# Schematic.net
KiCad netlist of a schematic drawn in EAGLE
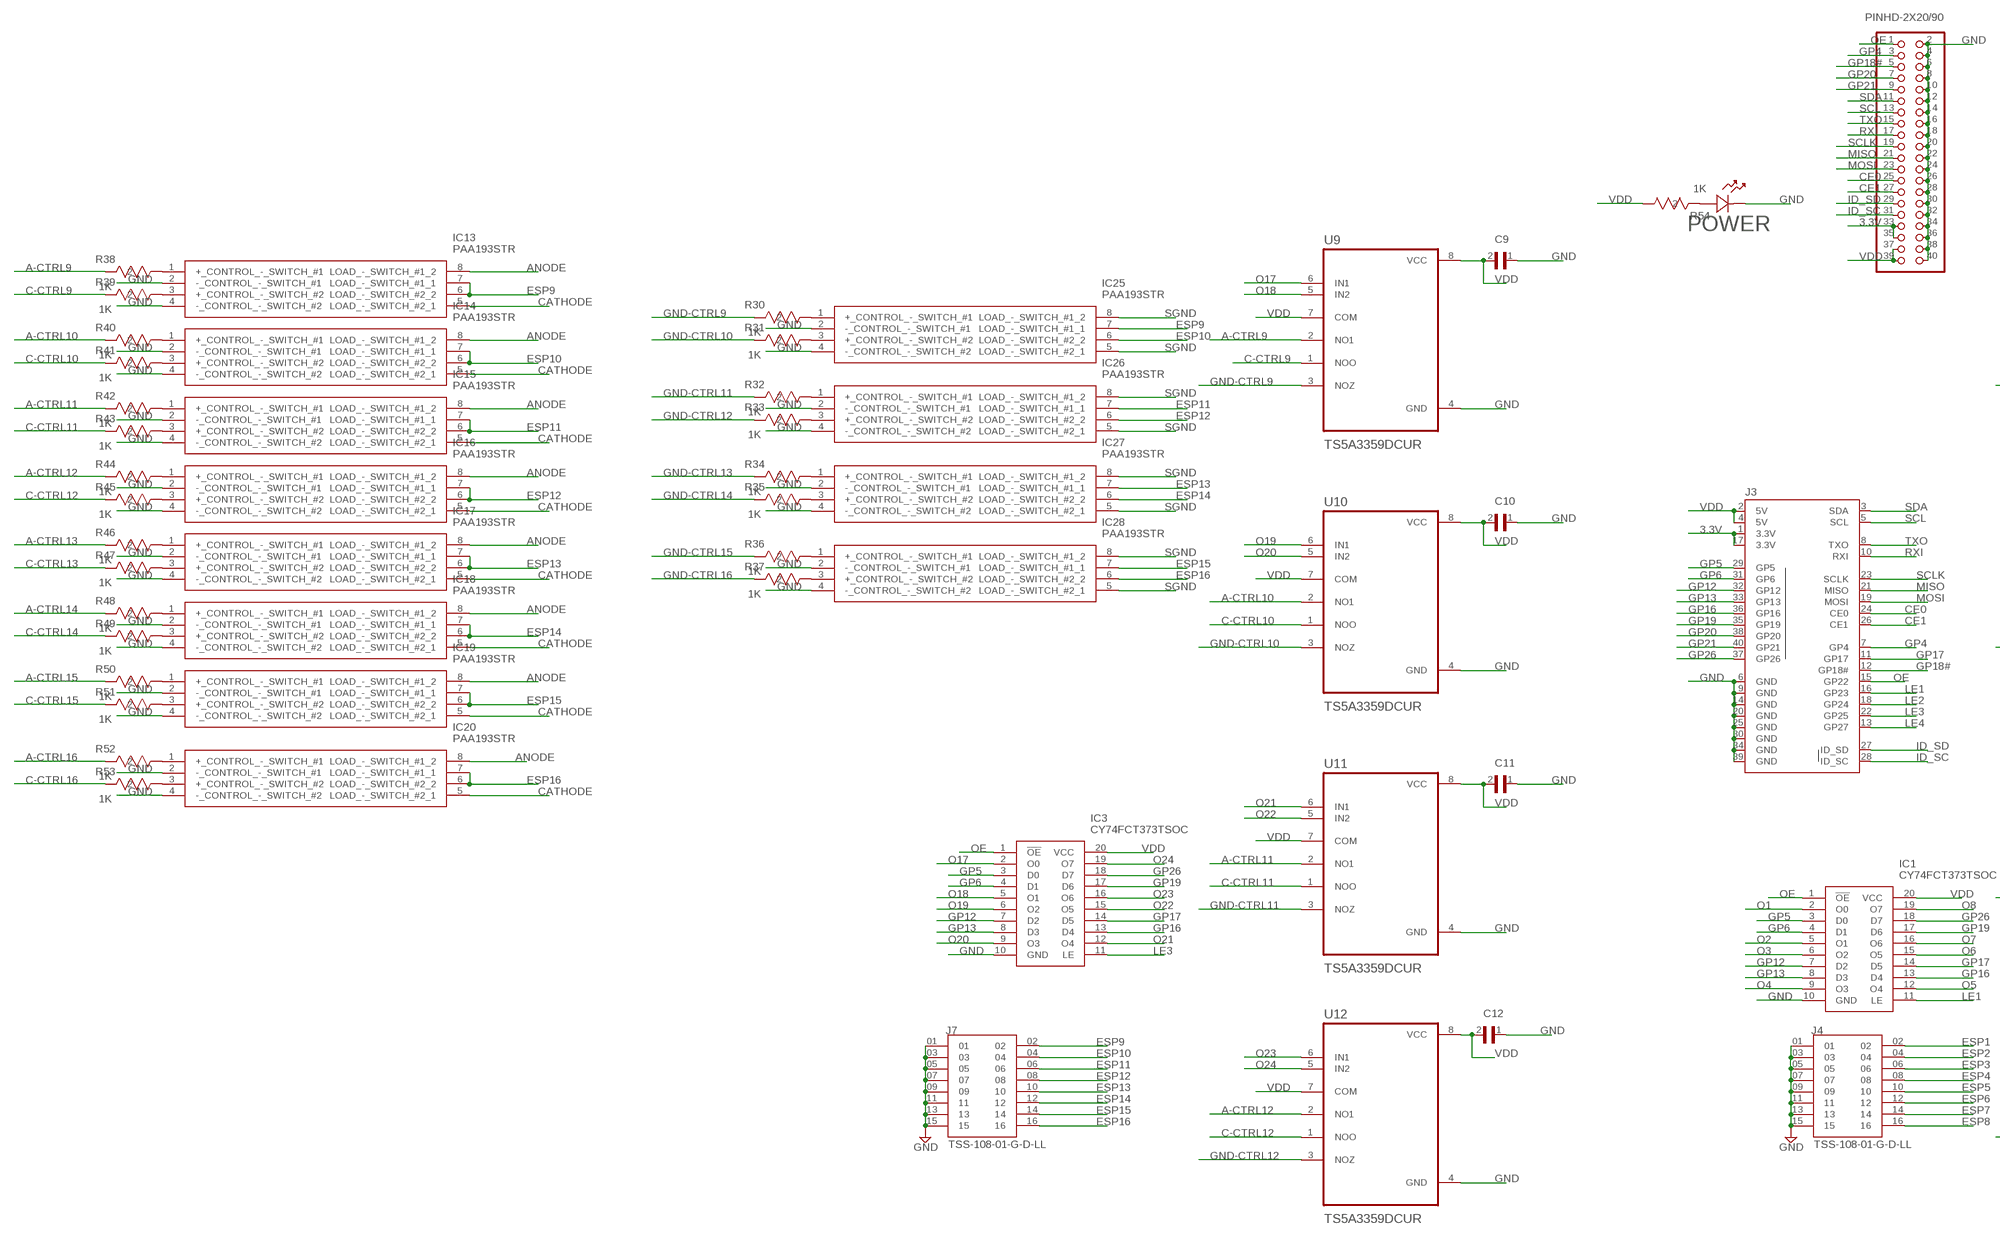
[diagram p0: schematic, sheet 1, part 1 of 3]
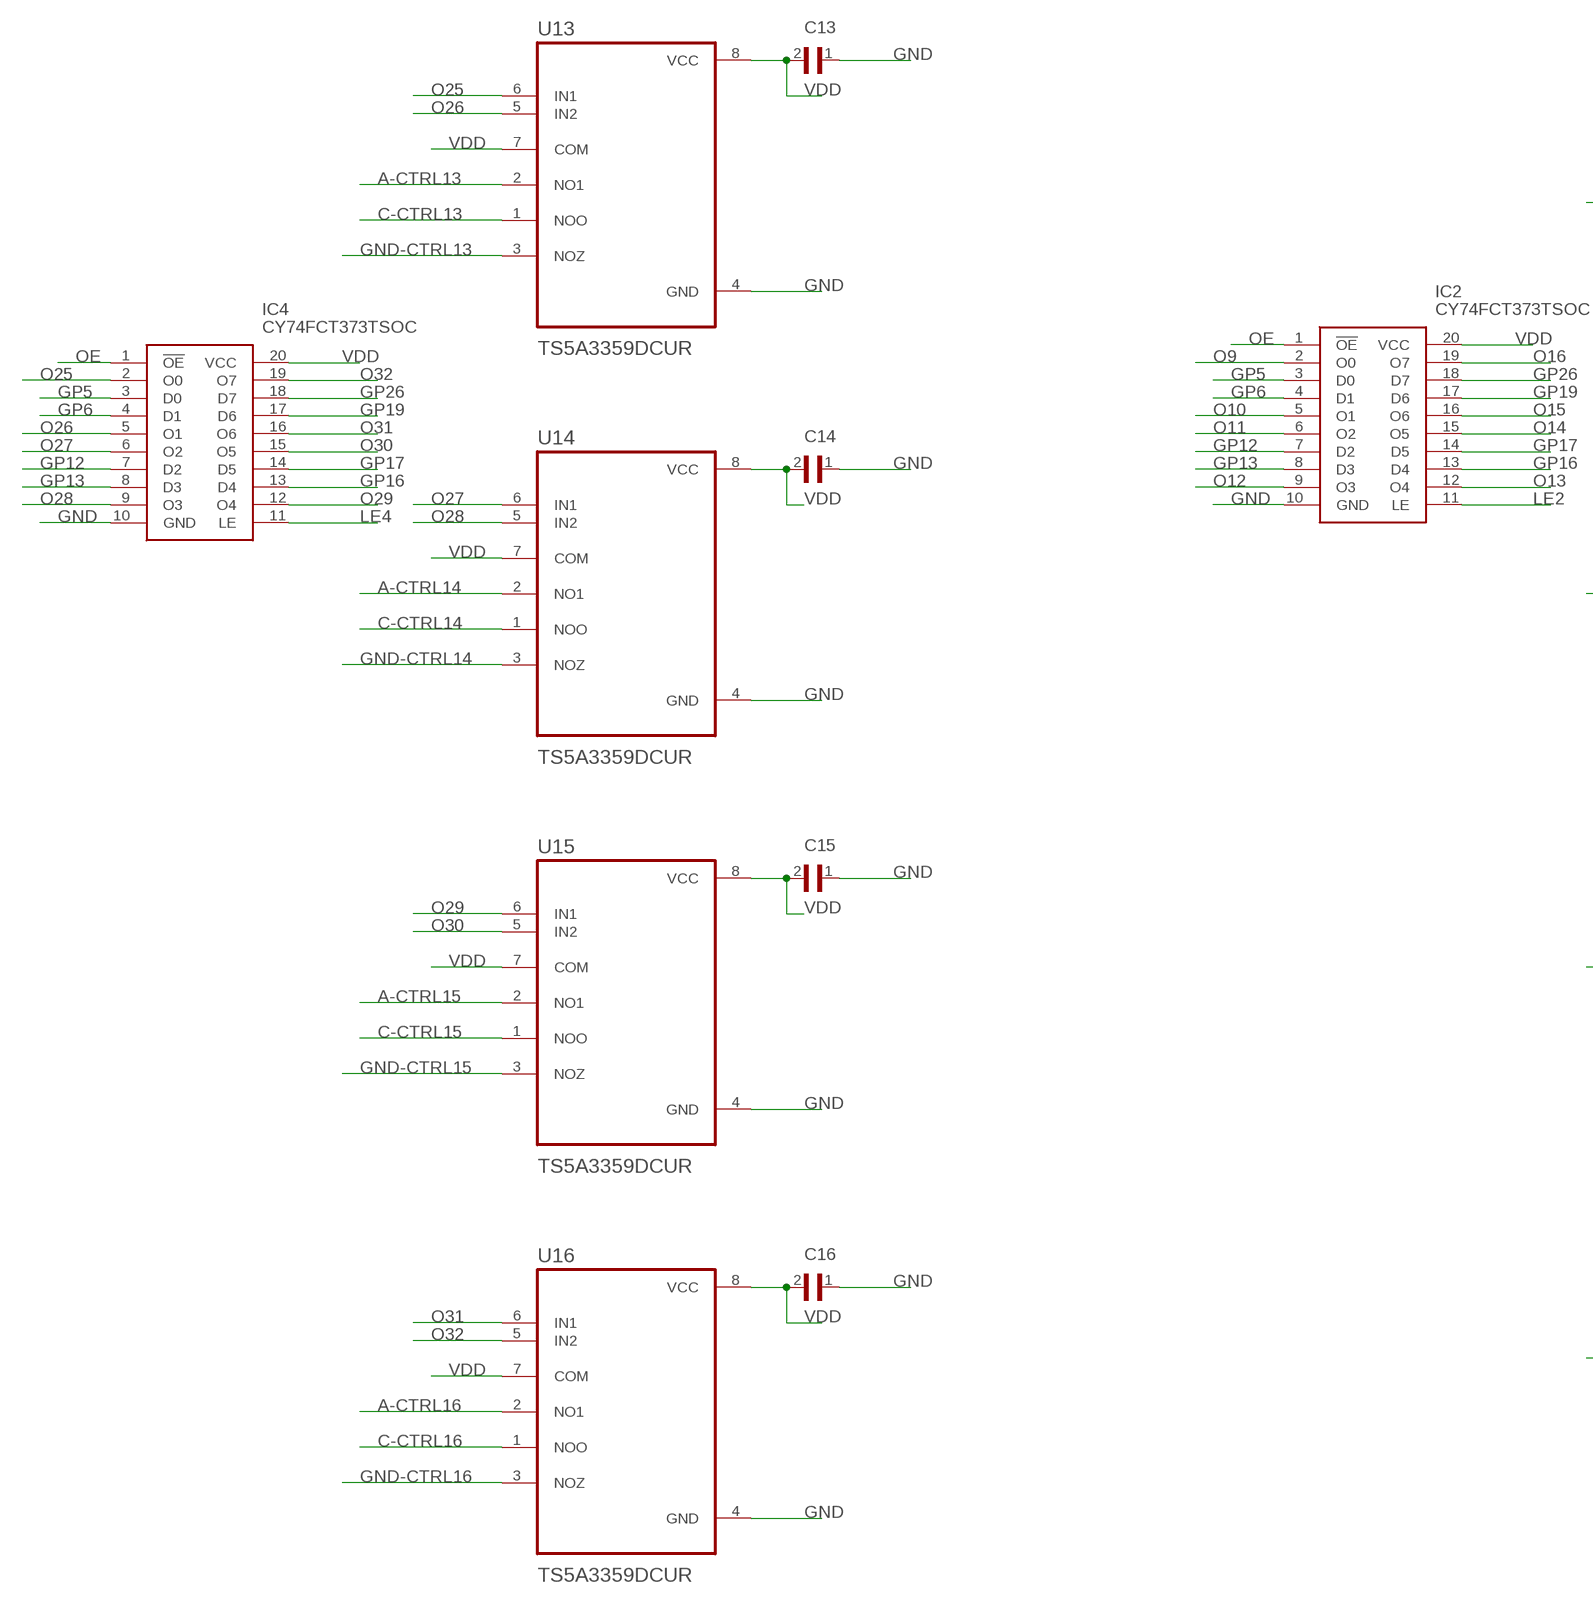
[diagram p1: schematic, sheet 1, part 2 of 3]
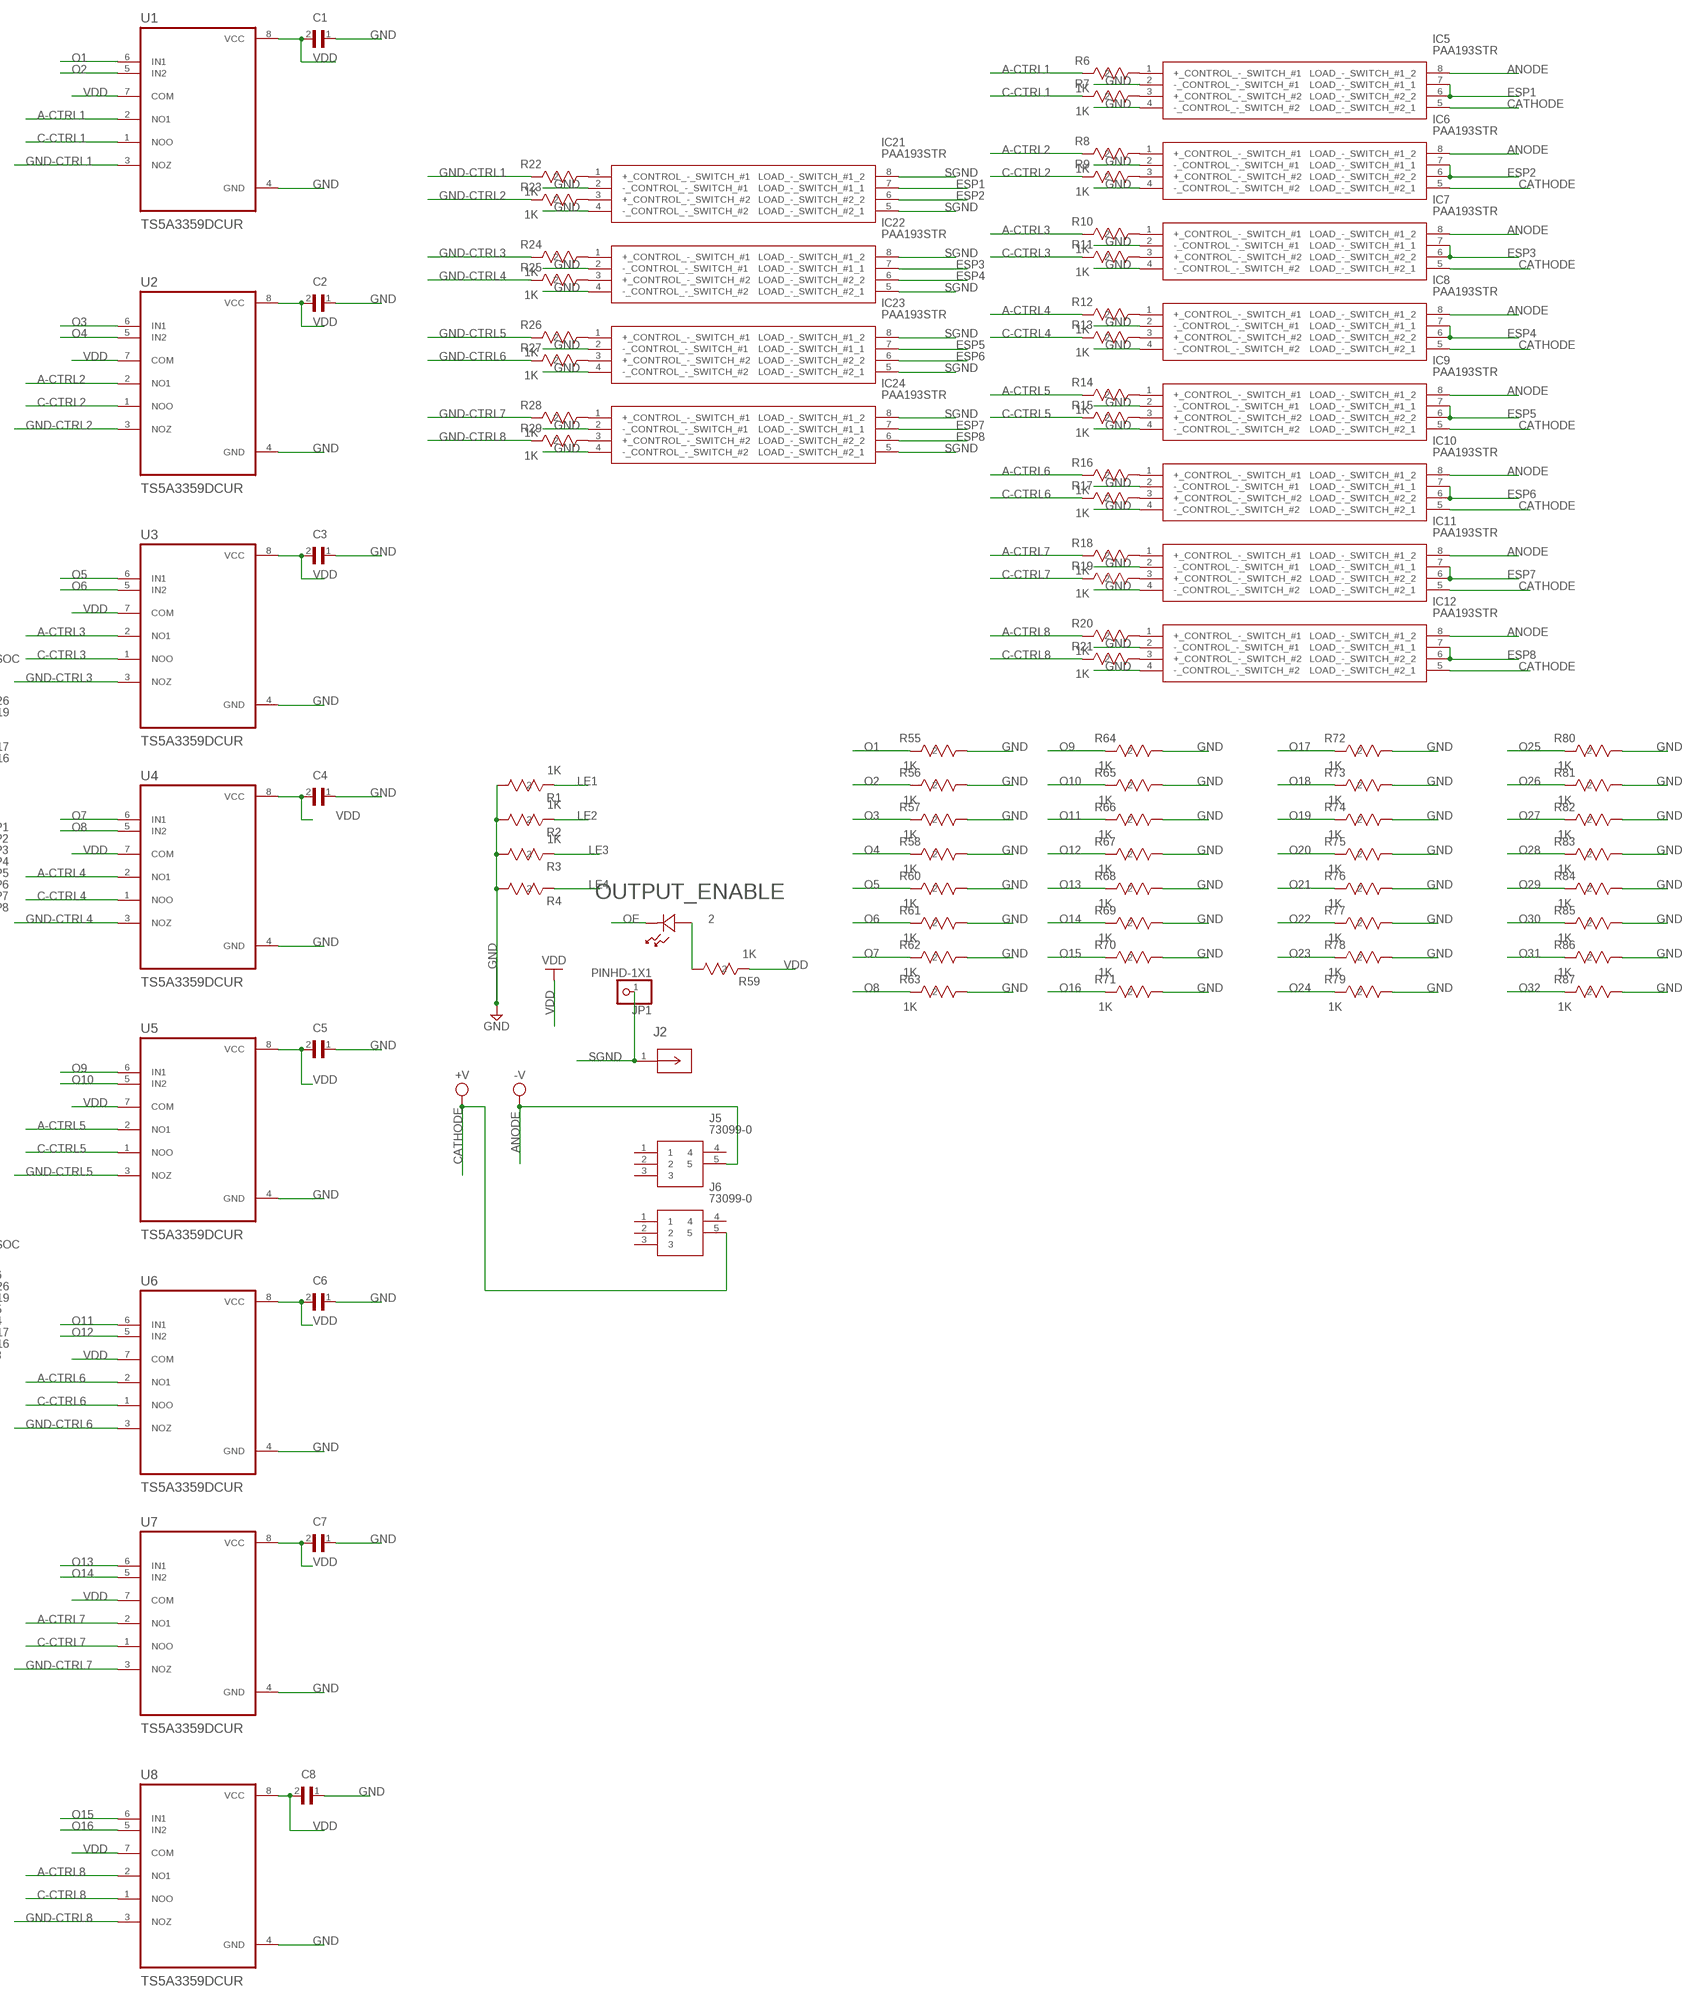
[diagram p2: schematic, sheet 1, part 3 of 3]

(export (version "E")
  (design (tool "Eeschema 10.0.6"))
  (components
    (comp (ref "C1")
      (value "CL05A104KA5NNNC")
      (footprint "eagle-import:CAPC1005X55N")
      (fields (field (name "MF") "Samsung Electro-Mechanics"))
      (libsource (lib "eagle-import") (part "CL05A104KA5NNNC"))
    )
    (comp (ref "C2")
      (value "CL05A104KA5NNNC")
      (footprint "eagle-import:CAPC1005X55N")
      (fields (field (name "MF") "Samsung Electro-Mechanics"))
      (libsource (lib "eagle-import") (part "CL05A104KA5NNNC"))
    )
    (comp (ref "C3")
      (value "CL05A104KA5NNNC")
      (footprint "eagle-import:CAPC1005X55N")
      (fields (field (name "MF") "Samsung Electro-Mechanics"))
      (libsource (lib "eagle-import") (part "CL05A104KA5NNNC"))
    )
    (comp (ref "C4")
      (value "CL05A104KA5NNNC")
      (footprint "eagle-import:CAPC1005X55N")
      (fields (field (name "MF") "Samsung Electro-Mechanics"))
      (libsource (lib "eagle-import") (part "CL05A104KA5NNNC"))
    )
    (comp (ref "C5")
      (value "CL05A104KA5NNNC")
      (footprint "eagle-import:CAPC1005X55N")
      (fields (field (name "MF") "Samsung Electro-Mechanics"))
      (libsource (lib "eagle-import") (part "CL05A104KA5NNNC"))
    )
    (comp (ref "C6")
      (value "CL05A104KA5NNNC")
      (footprint "eagle-import:CAPC1005X55N")
      (fields (field (name "MF") "Samsung Electro-Mechanics"))
      (libsource (lib "eagle-import") (part "CL05A104KA5NNNC"))
    )
    (comp (ref "C7")
      (value "CL05A104KA5NNNC")
      (footprint "eagle-import:CAPC1005X55N")
      (fields (field (name "MF") "Samsung Electro-Mechanics"))
      (libsource (lib "eagle-import") (part "CL05A104KA5NNNC"))
    )
    (comp (ref "C8")
      (value "CL05A104KA5NNNC")
      (footprint "eagle-import:CAPC1005X55N")
      (fields (field (name "MF") "Samsung Electro-Mechanics"))
      (libsource (lib "eagle-import") (part "CL05A104KA5NNNC"))
    )
    (comp (ref "C9")
      (value "CL05A104KA5NNNC")
      (footprint "eagle-import:CAPC1005X55N")
      (fields (field (name "MF") "Samsung Electro-Mechanics"))
      (libsource (lib "eagle-import") (part "CL05A104KA5NNNC"))
    )
    (comp (ref "C10")
      (value "CL05A104KA5NNNC")
      (footprint "eagle-import:CAPC1005X55N")
      (fields (field (name "MF") "Samsung Electro-Mechanics"))
      (libsource (lib "eagle-import") (part "CL05A104KA5NNNC"))
    )
    (comp (ref "C11")
      (value "CL05A104KA5NNNC")
      (footprint "eagle-import:CAPC1005X55N")
      (fields (field (name "MF") "Samsung Electro-Mechanics"))
      (libsource (lib "eagle-import") (part "CL05A104KA5NNNC"))
    )
    (comp (ref "C12")
      (value "CL05A104KA5NNNC")
      (footprint "eagle-import:CAPC1005X55N")
      (fields (field (name "MF") "Samsung Electro-Mechanics"))
      (libsource (lib "eagle-import") (part "CL05A104KA5NNNC"))
    )
    (comp (ref "C13")
      (value "CL05A104KA5NNNC")
      (footprint "eagle-import:CAPC1005X55N")
      (fields (field (name "MF") "Samsung Electro-Mechanics"))
      (libsource (lib "eagle-import") (part "CL05A104KA5NNNC"))
    )
    (comp (ref "C14")
      (value "CL05A104KA5NNNC")
      (footprint "eagle-import:CAPC1005X55N")
      (fields (field (name "MF") "Samsung Electro-Mechanics"))
      (libsource (lib "eagle-import") (part "CL05A104KA5NNNC"))
    )
    (comp (ref "C15")
      (value "CL05A104KA5NNNC")
      (footprint "eagle-import:CAPC1005X55N")
      (fields (field (name "MF") "Samsung Electro-Mechanics"))
      (libsource (lib "eagle-import") (part "CL05A104KA5NNNC"))
    )
    (comp (ref "C16")
      (value "CL05A104KA5NNNC")
      (footprint "eagle-import:CAPC1005X55N")
      (fields (field (name "MF") "Samsung Electro-Mechanics"))
      (libsource (lib "eagle-import") (part "CL05A104KA5NNNC"))
    )
    (comp (ref "IC1")
      (value "CY74FCT373TSOC")
      (footprint "eagle-import:SOIC127P1030X265-20N")
      (libsource (lib "eagle-import") (part "CY74FCT373TSOC"))
    )
    (comp (ref "IC2")
      (value "CY74FCT373TSOC")
      (footprint "eagle-import:SOIC127P1030X265-20N")
      (libsource (lib "eagle-import") (part "CY74FCT373TSOC"))
    )
    (comp (ref "IC3")
      (value "CY74FCT373TSOC")
      (footprint "eagle-import:SOIC127P1030X265-20N")
      (libsource (lib "eagle-import") (part "CY74FCT373TSOC"))
    )
    (comp (ref "IC4")
      (value "CY74FCT373TSOC")
      (footprint "eagle-import:SOIC127P1030X265-20N")
      (libsource (lib "eagle-import") (part "CY74FCT373TSOC"))
    )
    (comp (ref "IC5")
      (value "PAA193STR")
      (footprint "eagle-import:SOP254P952X457-8N")
      (fields (field (name "MOUSER_PART_NUMBER") "849-PAA193STR"))
      (libsource (lib "eagle-import") (part "PAA193STR"))
    )
    (comp (ref "IC6")
      (value "PAA193STR")
      (footprint "eagle-import:SOP254P952X457-8N")
      (fields (field (name "MOUSER_PART_NUMBER") "849-PAA193STR"))
      (libsource (lib "eagle-import") (part "PAA193STR"))
    )
    (comp (ref "IC7")
      (value "PAA193STR")
      (footprint "eagle-import:SOP254P952X457-8N")
      (fields (field (name "MOUSER_PART_NUMBER") "849-PAA193STR"))
      (libsource (lib "eagle-import") (part "PAA193STR"))
    )
    (comp (ref "IC8")
      (value "PAA193STR")
      (footprint "eagle-import:SOP254P952X457-8N")
      (fields (field (name "MOUSER_PART_NUMBER") "849-PAA193STR"))
      (libsource (lib "eagle-import") (part "PAA193STR"))
    )
    (comp (ref "IC9")
      (value "PAA193STR")
      (footprint "eagle-import:SOP254P952X457-8N")
      (fields (field (name "MOUSER_PART_NUMBER") "849-PAA193STR"))
      (libsource (lib "eagle-import") (part "PAA193STR"))
    )
    (comp (ref "IC10")
      (value "PAA193STR")
      (footprint "eagle-import:SOP254P952X457-8N")
      (fields (field (name "MOUSER_PART_NUMBER") "849-PAA193STR"))
      (libsource (lib "eagle-import") (part "PAA193STR"))
    )
    (comp (ref "IC11")
      (value "PAA193STR")
      (footprint "eagle-import:SOP254P952X457-8N")
      (fields (field (name "MOUSER_PART_NUMBER") "849-PAA193STR"))
      (libsource (lib "eagle-import") (part "PAA193STR"))
    )
    (comp (ref "IC12")
      (value "PAA193STR")
      (footprint "eagle-import:SOP254P952X457-8N")
      (fields (field (name "MOUSER_PART_NUMBER") "849-PAA193STR"))
      (libsource (lib "eagle-import") (part "PAA193STR"))
    )
    (comp (ref "IC13")
      (value "PAA193STR")
      (footprint "eagle-import:SOP254P952X457-8N")
      (fields (field (name "MOUSER_PART_NUMBER") "849-PAA193STR"))
      (libsource (lib "eagle-import") (part "PAA193STR"))
    )
    (comp (ref "IC14")
      (value "PAA193STR")
      (footprint "eagle-import:SOP254P952X457-8N")
      (fields (field (name "MOUSER_PART_NUMBER") "849-PAA193STR"))
      (libsource (lib "eagle-import") (part "PAA193STR"))
    )
    (comp (ref "IC15")
      (value "PAA193STR")
      (footprint "eagle-import:SOP254P952X457-8N")
      (fields (field (name "MOUSER_PART_NUMBER") "849-PAA193STR"))
      (libsource (lib "eagle-import") (part "PAA193STR"))
    )
    (comp (ref "IC16")
      (value "PAA193STR")
      (footprint "eagle-import:SOP254P952X457-8N")
      (fields (field (name "MOUSER_PART_NUMBER") "849-PAA193STR"))
      (libsource (lib "eagle-import") (part "PAA193STR"))
    )
    (comp (ref "IC17")
      (value "PAA193STR")
      (footprint "eagle-import:SOP254P952X457-8N")
      (fields (field (name "MOUSER_PART_NUMBER") "849-PAA193STR"))
      (libsource (lib "eagle-import") (part "PAA193STR"))
    )
    (comp (ref "IC18")
      (value "PAA193STR")
      (footprint "eagle-import:SOP254P952X457-8N")
      (fields (field (name "MOUSER_PART_NUMBER") "849-PAA193STR"))
      (libsource (lib "eagle-import") (part "PAA193STR"))
    )
    (comp (ref "IC19")
      (value "PAA193STR")
      (footprint "eagle-import:SOP254P952X457-8N")
      (fields (field (name "MOUSER_PART_NUMBER") "849-PAA193STR"))
      (libsource (lib "eagle-import") (part "PAA193STR"))
    )
    (comp (ref "IC20")
      (value "PAA193STR")
      (footprint "eagle-import:SOP254P952X457-8N")
      (fields (field (name "MOUSER_PART_NUMBER") "849-PAA193STR"))
      (libsource (lib "eagle-import") (part "PAA193STR"))
    )
    (comp (ref "IC21")
      (value "PAA193STR")
      (footprint "eagle-import:SOP254P952X457-8N")
      (fields (field (name "MOUSER_PART_NUMBER") "849-PAA193STR"))
      (libsource (lib "eagle-import") (part "PAA193STR"))
    )
    (comp (ref "IC22")
      (value "PAA193STR")
      (footprint "eagle-import:SOP254P952X457-8N")
      (fields (field (name "MOUSER_PART_NUMBER") "849-PAA193STR"))
      (libsource (lib "eagle-import") (part "PAA193STR"))
    )
    (comp (ref "IC23")
      (value "PAA193STR")
      (footprint "eagle-import:SOP254P952X457-8N")
      (fields (field (name "MOUSER_PART_NUMBER") "849-PAA193STR"))
      (libsource (lib "eagle-import") (part "PAA193STR"))
    )
    (comp (ref "IC24")
      (value "PAA193STR")
      (footprint "eagle-import:SOP254P952X457-8N")
      (fields (field (name "MOUSER_PART_NUMBER") "849-PAA193STR"))
      (libsource (lib "eagle-import") (part "PAA193STR"))
    )
    (comp (ref "IC25")
      (value "PAA193STR")
      (footprint "eagle-import:SOP254P952X457-8N")
      (fields (field (name "MOUSER_PART_NUMBER") "849-PAA193STR"))
      (libsource (lib "eagle-import") (part "PAA193STR"))
    )
    (comp (ref "IC26")
      (value "PAA193STR")
      (footprint "eagle-import:SOP254P952X457-8N")
      (fields (field (name "MOUSER_PART_NUMBER") "849-PAA193STR"))
      (libsource (lib "eagle-import") (part "PAA193STR"))
    )
    (comp (ref "IC27")
      (value "PAA193STR")
      (footprint "eagle-import:SOP254P952X457-8N")
      (fields (field (name "MOUSER_PART_NUMBER") "849-PAA193STR"))
      (libsource (lib "eagle-import") (part "PAA193STR"))
    )
    (comp (ref "IC28")
      (value "PAA193STR")
      (footprint "eagle-import:SOP254P952X457-8N")
      (fields (field (name "MOUSER_PART_NUMBER") "849-PAA193STR"))
      (libsource (lib "eagle-import") (part "PAA193STR"))
    )
    (comp (ref "J2")
      (value "FCR7350GCONN_FCR7350G_CLF")
      (footprint "eagle-import:CONN_FCR7350G_CLF")
      (fields
        (field (name "MANUFACTURER_PART_NUMBER") "FCR7350G")
        (field (name "COPYRIGHT") "Copyright (C) 2024 Ultra Librarian. All rights reserved.")
      )
      (libsource (lib "eagle-import") (part "FCR7350GCONN_FCR7350G_CLF"))
    )
    (comp (ref "J3")
      (value "RASPBERRYPI-40-PIN-GPIO_PTH_NO_SHROUD")
      (footprint "eagle-import:2X20")
      (fields (field (name "SPICEPREFIX") "X"))
      (libsource (lib "eagle-import") (part "RASPBERRYPI-40-PIN-GPIO_PTH_NO_SHROUD"))
    )
    (comp (ref "J4")
      (value "TSS-108-01-G-D-LL")
      (footprint "eagle-import:SAMTEC_TSS-108-01-G-D-LL")
      (libsource (lib "eagle-import") (part "TSS-108-01-G-D-LL"))
    )
    (comp (ref "J5")
      (value "73099-0")
      (footprint "eagle-import:730990")
      (fields (field (name "MOUSER_PART_NUMBER") "565-73099-0"))
      (libsource (lib "eagle-import") (part "73099-0"))
    )
    (comp (ref "J6")
      (value "73099-0")
      (footprint "eagle-import:730990")
      (fields (field (name "MOUSER_PART_NUMBER") "565-73099-0"))
      (libsource (lib "eagle-import") (part "73099-0"))
    )
    (comp (ref "J7")
      (value "TSS-108-01-G-D-LL")
      (footprint "eagle-import:SAMTEC_TSS-108-01-G-D-LL")
      (libsource (lib "eagle-import") (part "TSS-108-01-G-D-LL"))
    )
    (comp (ref "JP1")
      (value "PINHD-1X1")
      (footprint "eagle-import:1X01")
      (fields (field (name "MANUFACTURER") "Generic"))
      (libsource (lib "eagle-import") (part "PINHD-1X1"))
    )
    (comp (ref "JP4")
      (value "PINHD-2X20/90")
      (footprint "eagle-import:2X20_90")
      (fields (field (name "MANUFACTURER") "Generic"))
      (libsource (lib "eagle-import") (part "PINHD-2X20/90"))
    )
    (comp (ref "OUTPUT_ENABLE")
      (value "LTST-C190GKTLED_LTST-C190CKT_LTO")
      (footprint "eagle-import:LED_LTST-C190CKT_LTO")
      (fields
        (field (name "MANUFACTURER_PART_NUMBER") "LTST-C190GKT")
        (field (name "COPYRIGHT") "Copyright (C) 2024 Ultra Librarian. All rights reserved.")
      )
      (libsource (lib "eagle-import") (part "LTST-C190GKTLED_LTST-C190CKT_LTO"))
    )
    (comp (ref "POWER")
      (value "LTST-C190GKTLED_LTST-C190CKT_LTO")
      (footprint "eagle-import:LED_LTST-C190CKT_LTO")
      (fields
        (field (name "MANUFACTURER_PART_NUMBER") "LTST-C190GKT")
        (field (name "COPYRIGHT") "Copyright (C) 2024 Ultra Librarian. All rights reserved.")
      )
      (libsource (lib "eagle-import") (part "LTST-C190GKTLED_LTST-C190CKT_LTO"))
    )
    (comp (ref "R1")
      (value "1K")
      (footprint "eagle-import:RC0402N_YAG")
      (fields
        (field (name "MANUFACTURER_PART_NUMBER") "RC0402JR-071KL")
        (field (name "COPYRIGHT") "Copyright (C) 2023 Ultra Librarian. All rights reserved.")
      )
      (libsource (lib "eagle-import") (part "RC0402JR-071KLRC0402N_YAG"))
    )
    (comp (ref "R2")
      (value "1K")
      (footprint "eagle-import:RC0402N_YAG")
      (fields
        (field (name "MANUFACTURER_PART_NUMBER") "RC0402JR-071KL")
        (field (name "COPYRIGHT") "Copyright (C) 2023 Ultra Librarian. All rights reserved.")
      )
      (libsource (lib "eagle-import") (part "RC0402JR-071KLRC0402N_YAG"))
    )
    (comp (ref "R3")
      (value "1K")
      (footprint "eagle-import:RC0402N_YAG")
      (fields
        (field (name "MANUFACTURER_PART_NUMBER") "RC0402JR-071KL")
        (field (name "COPYRIGHT") "Copyright (C) 2023 Ultra Librarian. All rights reserved.")
      )
      (libsource (lib "eagle-import") (part "RC0402JR-071KLRC0402N_YAG"))
    )
    (comp (ref "R4")
      (value "RC0402JR-071KLRC0402N_YAG")
      (footprint "eagle-import:RC0402N_YAG")
      (fields
        (field (name "MANUFACTURER_PART_NUMBER") "RC0402JR-071KL")
        (field (name "COPYRIGHT") "Copyright (C) 2023 Ultra Librarian. All rights reserved.")
      )
      (libsource (lib "eagle-import") (part "RC0402JR-071KLRC0402N_YAG"))
    )
    (comp (ref "R6")
      (value "1K")
      (footprint "eagle-import:RC0402N_YAG")
      (fields
        (field (name "MANUFACTURER_PART_NUMBER") "RC0402JR-071KL")
        (field (name "COPYRIGHT") "Copyright (C) 2023 Ultra Librarian. All rights reserved.")
      )
      (libsource (lib "eagle-import") (part "RC0402JR-071KLRC0402N_YAG"))
    )
    (comp (ref "R7")
      (value "1K")
      (footprint "eagle-import:RC0402N_YAG")
      (fields
        (field (name "MANUFACTURER_PART_NUMBER") "RC0402JR-071KL")
        (field (name "COPYRIGHT") "Copyright (C) 2023 Ultra Librarian. All rights reserved.")
      )
      (libsource (lib "eagle-import") (part "RC0402JR-071KLRC0402N_YAG"))
    )
    (comp (ref "R8")
      (value "1K")
      (footprint "eagle-import:RC0402N_YAG")
      (fields
        (field (name "MANUFACTURER_PART_NUMBER") "RC0402JR-071KL")
        (field (name "COPYRIGHT") "Copyright (C) 2023 Ultra Librarian. All rights reserved.")
      )
      (libsource (lib "eagle-import") (part "RC0402JR-071KLRC0402N_YAG"))
    )
    (comp (ref "R9")
      (value "1K")
      (footprint "eagle-import:RC0402N_YAG")
      (fields
        (field (name "MANUFACTURER_PART_NUMBER") "RC0402JR-071KL")
        (field (name "COPYRIGHT") "Copyright (C) 2023 Ultra Librarian. All rights reserved.")
      )
      (libsource (lib "eagle-import") (part "RC0402JR-071KLRC0402N_YAG"))
    )
    (comp (ref "R10")
      (value "1K")
      (footprint "eagle-import:RC0402N_YAG")
      (fields
        (field (name "MANUFACTURER_PART_NUMBER") "RC0402JR-071KL")
        (field (name "COPYRIGHT") "Copyright (C) 2023 Ultra Librarian. All rights reserved.")
      )
      (libsource (lib "eagle-import") (part "RC0402JR-071KLRC0402N_YAG"))
    )
    (comp (ref "R11")
      (value "1K")
      (footprint "eagle-import:RC0402N_YAG")
      (fields
        (field (name "MANUFACTURER_PART_NUMBER") "RC0402JR-071KL")
        (field (name "COPYRIGHT") "Copyright (C) 2023 Ultra Librarian. All rights reserved.")
      )
      (libsource (lib "eagle-import") (part "RC0402JR-071KLRC0402N_YAG"))
    )
    (comp (ref "R12")
      (value "1K")
      (footprint "eagle-import:RC0402N_YAG")
      (fields
        (field (name "MANUFACTURER_PART_NUMBER") "RC0402JR-071KL")
        (field (name "COPYRIGHT") "Copyright (C) 2023 Ultra Librarian. All rights reserved.")
      )
      (libsource (lib "eagle-import") (part "RC0402JR-071KLRC0402N_YAG"))
    )
    (comp (ref "R13")
      (value "1K")
      (footprint "eagle-import:RC0402N_YAG")
      (fields
        (field (name "MANUFACTURER_PART_NUMBER") "RC0402JR-071KL")
        (field (name "COPYRIGHT") "Copyright (C) 2023 Ultra Librarian. All rights reserved.")
      )
      (libsource (lib "eagle-import") (part "RC0402JR-071KLRC0402N_YAG"))
    )
    (comp (ref "R14")
      (value "1K")
      (footprint "eagle-import:RC0402N_YAG")
      (fields
        (field (name "MANUFACTURER_PART_NUMBER") "RC0402JR-071KL")
        (field (name "COPYRIGHT") "Copyright (C) 2023 Ultra Librarian. All rights reserved.")
      )
      (libsource (lib "eagle-import") (part "RC0402JR-071KLRC0402N_YAG"))
    )
    (comp (ref "R15")
      (value "1K")
      (footprint "eagle-import:RC0402N_YAG")
      (fields
        (field (name "MANUFACTURER_PART_NUMBER") "RC0402JR-071KL")
        (field (name "COPYRIGHT") "Copyright (C) 2023 Ultra Librarian. All rights reserved.")
      )
      (libsource (lib "eagle-import") (part "RC0402JR-071KLRC0402N_YAG"))
    )
    (comp (ref "R16")
      (value "1K")
      (footprint "eagle-import:RC0402N_YAG")
      (fields
        (field (name "MANUFACTURER_PART_NUMBER") "RC0402JR-071KL")
        (field (name "COPYRIGHT") "Copyright (C) 2023 Ultra Librarian. All rights reserved.")
      )
      (libsource (lib "eagle-import") (part "RC0402JR-071KLRC0402N_YAG"))
    )
    (comp (ref "R17")
      (value "1K")
      (footprint "eagle-import:RC0402N_YAG")
      (fields
        (field (name "MANUFACTURER_PART_NUMBER") "RC0402JR-071KL")
        (field (name "COPYRIGHT") "Copyright (C) 2023 Ultra Librarian. All rights reserved.")
      )
      (libsource (lib "eagle-import") (part "RC0402JR-071KLRC0402N_YAG"))
    )
    (comp (ref "R18")
      (value "1K")
      (footprint "eagle-import:RC0402N_YAG")
      (fields
        (field (name "MANUFACTURER_PART_NUMBER") "RC0402JR-071KL")
        (field (name "COPYRIGHT") "Copyright (C) 2023 Ultra Librarian. All rights reserved.")
      )
      (libsource (lib "eagle-import") (part "RC0402JR-071KLRC0402N_YAG"))
    )
    (comp (ref "R19")
      (value "1K")
      (footprint "eagle-import:RC0402N_YAG")
      (fields
        (field (name "MANUFACTURER_PART_NUMBER") "RC0402JR-071KL")
        (field (name "COPYRIGHT") "Copyright (C) 2023 Ultra Librarian. All rights reserved.")
      )
      (libsource (lib "eagle-import") (part "RC0402JR-071KLRC0402N_YAG"))
    )
    (comp (ref "R20")
      (value "1K")
      (footprint "eagle-import:RC0402N_YAG")
      (fields
        (field (name "MANUFACTURER_PART_NUMBER") "RC0402JR-071KL")
        (field (name "COPYRIGHT") "Copyright (C) 2023 Ultra Librarian. All rights reserved.")
      )
      (libsource (lib "eagle-import") (part "RC0402JR-071KLRC0402N_YAG"))
    )
    (comp (ref "R21")
      (value "1K")
      (footprint "eagle-import:RC0402N_YAG")
      (fields
        (field (name "MANUFACTURER_PART_NUMBER") "RC0402JR-071KL")
        (field (name "COPYRIGHT") "Copyright (C) 2023 Ultra Librarian. All rights reserved.")
      )
      (libsource (lib "eagle-import") (part "RC0402JR-071KLRC0402N_YAG"))
    )
    (comp (ref "R22")
      (value "1K")
      (footprint "eagle-import:RC0402N_YAG")
      (fields
        (field (name "MANUFACTURER_PART_NUMBER") "RC0402JR-071KL")
        (field (name "COPYRIGHT") "Copyright (C) 2023 Ultra Librarian. All rights reserved.")
      )
      (libsource (lib "eagle-import") (part "RC0402JR-071KLRC0402N_YAG"))
    )
    (comp (ref "R23")
      (value "1K")
      (footprint "eagle-import:RC0402N_YAG")
      (fields
        (field (name "MANUFACTURER_PART_NUMBER") "RC0402JR-071KL")
        (field (name "COPYRIGHT") "Copyright (C) 2023 Ultra Librarian. All rights reserved.")
      )
      (libsource (lib "eagle-import") (part "RC0402JR-071KLRC0402N_YAG"))
    )
    (comp (ref "R24")
      (value "1K")
      (footprint "eagle-import:RC0402N_YAG")
      (fields
        (field (name "MANUFACTURER_PART_NUMBER") "RC0402JR-071KL")
        (field (name "COPYRIGHT") "Copyright (C) 2023 Ultra Librarian. All rights reserved.")
      )
      (libsource (lib "eagle-import") (part "RC0402JR-071KLRC0402N_YAG"))
    )
    (comp (ref "R25")
      (value "1K")
      (footprint "eagle-import:RC0402N_YAG")
      (fields
        (field (name "MANUFACTURER_PART_NUMBER") "RC0402JR-071KL")
        (field (name "COPYRIGHT") "Copyright (C) 2023 Ultra Librarian. All rights reserved.")
      )
      (libsource (lib "eagle-import") (part "RC0402JR-071KLRC0402N_YAG"))
    )
    (comp (ref "R26")
      (value "1K")
      (footprint "eagle-import:RC0402N_YAG")
      (fields
        (field (name "MANUFACTURER_PART_NUMBER") "RC0402JR-071KL")
        (field (name "COPYRIGHT") "Copyright (C) 2023 Ultra Librarian. All rights reserved.")
      )
      (libsource (lib "eagle-import") (part "RC0402JR-071KLRC0402N_YAG"))
    )
    (comp (ref "R27")
      (value "1K")
      (footprint "eagle-import:RC0402N_YAG")
      (fields
        (field (name "MANUFACTURER_PART_NUMBER") "RC0402JR-071KL")
        (field (name "COPYRIGHT") "Copyright (C) 2023 Ultra Librarian. All rights reserved.")
      )
      (libsource (lib "eagle-import") (part "RC0402JR-071KLRC0402N_YAG"))
    )
    (comp (ref "R28")
      (value "1K")
      (footprint "eagle-import:RC0402N_YAG")
      (fields
        (field (name "MANUFACTURER_PART_NUMBER") "RC0402JR-071KL")
        (field (name "COPYRIGHT") "Copyright (C) 2023 Ultra Librarian. All rights reserved.")
      )
      (libsource (lib "eagle-import") (part "RC0402JR-071KLRC0402N_YAG"))
    )
    (comp (ref "R29")
      (value "1K")
      (footprint "eagle-import:RC0402N_YAG")
      (fields
        (field (name "MANUFACTURER_PART_NUMBER") "RC0402JR-071KL")
        (field (name "COPYRIGHT") "Copyright (C) 2023 Ultra Librarian. All rights reserved.")
      )
      (libsource (lib "eagle-import") (part "RC0402JR-071KLRC0402N_YAG"))
    )
    (comp (ref "R30")
      (value "1K")
      (footprint "eagle-import:RC0402N_YAG")
      (fields
        (field (name "MANUFACTURER_PART_NUMBER") "RC0402JR-071KL")
        (field (name "COPYRIGHT") "Copyright (C) 2023 Ultra Librarian. All rights reserved.")
      )
      (libsource (lib "eagle-import") (part "RC0402JR-071KLRC0402N_YAG"))
    )
    (comp (ref "R31")
      (value "1K")
      (footprint "eagle-import:RC0402N_YAG")
      (fields
        (field (name "MANUFACTURER_PART_NUMBER") "RC0402JR-071KL")
        (field (name "COPYRIGHT") "Copyright (C) 2023 Ultra Librarian. All rights reserved.")
      )
      (libsource (lib "eagle-import") (part "RC0402JR-071KLRC0402N_YAG"))
    )
    (comp (ref "R32")
      (value "1K")
      (footprint "eagle-import:RC0402N_YAG")
      (fields
        (field (name "MANUFACTURER_PART_NUMBER") "RC0402JR-071KL")
        (field (name "COPYRIGHT") "Copyright (C) 2023 Ultra Librarian. All rights reserved.")
      )
      (libsource (lib "eagle-import") (part "RC0402JR-071KLRC0402N_YAG"))
    )
    (comp (ref "R33")
      (value "1K")
      (footprint "eagle-import:RC0402N_YAG")
      (fields
        (field (name "MANUFACTURER_PART_NUMBER") "RC0402JR-071KL")
        (field (name "COPYRIGHT") "Copyright (C) 2023 Ultra Librarian. All rights reserved.")
      )
      (libsource (lib "eagle-import") (part "RC0402JR-071KLRC0402N_YAG"))
    )
    (comp (ref "R34")
      (value "1K")
      (footprint "eagle-import:RC0402N_YAG")
      (fields
        (field (name "MANUFACTURER_PART_NUMBER") "RC0402JR-071KL")
        (field (name "COPYRIGHT") "Copyright (C) 2023 Ultra Librarian. All rights reserved.")
      )
      (libsource (lib "eagle-import") (part "RC0402JR-071KLRC0402N_YAG"))
    )
    (comp (ref "R35")
      (value "1K")
      (footprint "eagle-import:RC0402N_YAG")
      (fields
        (field (name "MANUFACTURER_PART_NUMBER") "RC0402JR-071KL")
        (field (name "COPYRIGHT") "Copyright (C) 2023 Ultra Librarian. All rights reserved.")
      )
      (libsource (lib "eagle-import") (part "RC0402JR-071KLRC0402N_YAG"))
    )
    (comp (ref "R36")
      (value "1K")
      (footprint "eagle-import:RC0402N_YAG")
      (fields
        (field (name "MANUFACTURER_PART_NUMBER") "RC0402JR-071KL")
        (field (name "COPYRIGHT") "Copyright (C) 2023 Ultra Librarian. All rights reserved.")
      )
      (libsource (lib "eagle-import") (part "RC0402JR-071KLRC0402N_YAG"))
    )
    (comp (ref "R37")
      (value "1K")
      (footprint "eagle-import:RC0402N_YAG")
      (fields
        (field (name "MANUFACTURER_PART_NUMBER") "RC0402JR-071KL")
        (field (name "COPYRIGHT") "Copyright (C) 2023 Ultra Librarian. All rights reserved.")
      )
      (libsource (lib "eagle-import") (part "RC0402JR-071KLRC0402N_YAG"))
    )
    (comp (ref "R38")
      (value "1K")
      (footprint "eagle-import:RC0402N_YAG")
      (fields
        (field (name "MANUFACTURER_PART_NUMBER") "RC0402JR-071KL")
        (field (name "COPYRIGHT") "Copyright (C) 2023 Ultra Librarian. All rights reserved.")
      )
      (libsource (lib "eagle-import") (part "RC0402JR-071KLRC0402N_YAG"))
    )
    (comp (ref "R39")
      (value "1K")
      (footprint "eagle-import:RC0402N_YAG")
      (fields
        (field (name "MANUFACTURER_PART_NUMBER") "RC0402JR-071KL")
        (field (name "COPYRIGHT") "Copyright (C) 2023 Ultra Librarian. All rights reserved.")
      )
      (libsource (lib "eagle-import") (part "RC0402JR-071KLRC0402N_YAG"))
    )
    (comp (ref "R40")
      (value "1K")
      (footprint "eagle-import:RC0402N_YAG")
      (fields
        (field (name "MANUFACTURER_PART_NUMBER") "RC0402JR-071KL")
        (field (name "COPYRIGHT") "Copyright (C) 2023 Ultra Librarian. All rights reserved.")
      )
      (libsource (lib "eagle-import") (part "RC0402JR-071KLRC0402N_YAG"))
    )
    (comp (ref "R41")
      (value "1K")
      (footprint "eagle-import:RC0402N_YAG")
      (fields
        (field (name "MANUFACTURER_PART_NUMBER") "RC0402JR-071KL")
        (field (name "COPYRIGHT") "Copyright (C) 2023 Ultra Librarian. All rights reserved.")
      )
      (libsource (lib "eagle-import") (part "RC0402JR-071KLRC0402N_YAG"))
    )
    (comp (ref "R42")
      (value "1K")
      (footprint "eagle-import:RC0402N_YAG")
      (fields
        (field (name "MANUFACTURER_PART_NUMBER") "RC0402JR-071KL")
        (field (name "COPYRIGHT") "Copyright (C) 2023 Ultra Librarian. All rights reserved.")
      )
      (libsource (lib "eagle-import") (part "RC0402JR-071KLRC0402N_YAG"))
    )
    (comp (ref "R43")
      (value "1K")
      (footprint "eagle-import:RC0402N_YAG")
      (fields
        (field (name "MANUFACTURER_PART_NUMBER") "RC0402JR-071KL")
        (field (name "COPYRIGHT") "Copyright (C) 2023 Ultra Librarian. All rights reserved.")
      )
      (libsource (lib "eagle-import") (part "RC0402JR-071KLRC0402N_YAG"))
    )
    (comp (ref "R44")
      (value "1K")
      (footprint "eagle-import:RC0402N_YAG")
      (fields
        (field (name "MANUFACTURER_PART_NUMBER") "RC0402JR-071KL")
        (field (name "COPYRIGHT") "Copyright (C) 2023 Ultra Librarian. All rights reserved.")
      )
      (libsource (lib "eagle-import") (part "RC0402JR-071KLRC0402N_YAG"))
    )
    (comp (ref "R45")
      (value "1K")
      (footprint "eagle-import:RC0402N_YAG")
      (fields
        (field (name "MANUFACTURER_PART_NUMBER") "RC0402JR-071KL")
        (field (name "COPYRIGHT") "Copyright (C) 2023 Ultra Librarian. All rights reserved.")
      )
      (libsource (lib "eagle-import") (part "RC0402JR-071KLRC0402N_YAG"))
    )
    (comp (ref "R46")
      (value "1K")
      (footprint "eagle-import:RC0402N_YAG")
      (fields
        (field (name "MANUFACTURER_PART_NUMBER") "RC0402JR-071KL")
        (field (name "COPYRIGHT") "Copyright (C) 2023 Ultra Librarian. All rights reserved.")
      )
      (libsource (lib "eagle-import") (part "RC0402JR-071KLRC0402N_YAG"))
    )
    (comp (ref "R47")
      (value "1K")
      (footprint "eagle-import:RC0402N_YAG")
      (fields
        (field (name "MANUFACTURER_PART_NUMBER") "RC0402JR-071KL")
        (field (name "COPYRIGHT") "Copyright (C) 2023 Ultra Librarian. All rights reserved.")
      )
      (libsource (lib "eagle-import") (part "RC0402JR-071KLRC0402N_YAG"))
    )
    (comp (ref "R48")
      (value "1K")
      (footprint "eagle-import:RC0402N_YAG")
      (fields
        (field (name "MANUFACTURER_PART_NUMBER") "RC0402JR-071KL")
        (field (name "COPYRIGHT") "Copyright (C) 2023 Ultra Librarian. All rights reserved.")
      )
      (libsource (lib "eagle-import") (part "RC0402JR-071KLRC0402N_YAG"))
    )
    (comp (ref "R49")
      (value "1K")
      (footprint "eagle-import:RC0402N_YAG")
      (fields
        (field (name "MANUFACTURER_PART_NUMBER") "RC0402JR-071KL")
        (field (name "COPYRIGHT") "Copyright (C) 2023 Ultra Librarian. All rights reserved.")
      )
      (libsource (lib "eagle-import") (part "RC0402JR-071KLRC0402N_YAG"))
    )
    (comp (ref "R50")
      (value "1K")
      (footprint "eagle-import:RC0402N_YAG")
      (fields
        (field (name "MANUFACTURER_PART_NUMBER") "RC0402JR-071KL")
        (field (name "COPYRIGHT") "Copyright (C) 2023 Ultra Librarian. All rights reserved.")
      )
      (libsource (lib "eagle-import") (part "RC0402JR-071KLRC0402N_YAG"))
    )
    (comp (ref "R51")
      (value "1K")
      (footprint "eagle-import:RC0402N_YAG")
      (fields
        (field (name "MANUFACTURER_PART_NUMBER") "RC0402JR-071KL")
        (field (name "COPYRIGHT") "Copyright (C) 2023 Ultra Librarian. All rights reserved.")
      )
      (libsource (lib "eagle-import") (part "RC0402JR-071KLRC0402N_YAG"))
    )
    (comp (ref "R52")
      (value "1K")
      (footprint "eagle-import:RC0402N_YAG")
      (fields
        (field (name "MANUFACTURER_PART_NUMBER") "RC0402JR-071KL")
        (field (name "COPYRIGHT") "Copyright (C) 2023 Ultra Librarian. All rights reserved.")
      )
      (libsource (lib "eagle-import") (part "RC0402JR-071KLRC0402N_YAG"))
    )
    (comp (ref "R53")
      (value "1K")
      (footprint "eagle-import:RC0402N_YAG")
      (fields
        (field (name "MANUFACTURER_PART_NUMBER") "RC0402JR-071KL")
        (field (name "COPYRIGHT") "Copyright (C) 2023 Ultra Librarian. All rights reserved.")
      )
      (libsource (lib "eagle-import") (part "RC0402JR-071KLRC0402N_YAG"))
    )
    (comp (ref "R54")
      (value "1K")
      (footprint "eagle-import:RC0402N_YAG")
      (fields
        (field (name "MANUFACTURER_PART_NUMBER") "RC0402JR-071KL")
        (field (name "COPYRIGHT") "Copyright (C) 2023 Ultra Librarian. All rights reserved.")
      )
      (libsource (lib "eagle-import") (part "RC0402JR-071KLRC0402N_YAG"))
    )
    (comp (ref "R55")
      (value "1K")
      (footprint "eagle-import:RC0402N_YAG")
      (fields
        (field (name "MANUFACTURER_PART_NUMBER") "RC0402JR-071KL")
        (field (name "COPYRIGHT") "Copyright (C) 2023 Ultra Librarian. All rights reserved.")
      )
      (libsource (lib "eagle-import") (part "RC0402JR-071KLRC0402N_YAG"))
    )
    (comp (ref "R56")
      (value "1K")
      (footprint "eagle-import:RC0402N_YAG")
      (fields
        (field (name "MANUFACTURER_PART_NUMBER") "RC0402JR-071KL")
        (field (name "COPYRIGHT") "Copyright (C) 2023 Ultra Librarian. All rights reserved.")
      )
      (libsource (lib "eagle-import") (part "RC0402JR-071KLRC0402N_YAG"))
    )
    (comp (ref "R57")
      (value "1K")
      (footprint "eagle-import:RC0402N_YAG")
      (fields
        (field (name "MANUFACTURER_PART_NUMBER") "RC0402JR-071KL")
        (field (name "COPYRIGHT") "Copyright (C) 2023 Ultra Librarian. All rights reserved.")
      )
      (libsource (lib "eagle-import") (part "RC0402JR-071KLRC0402N_YAG"))
    )
    (comp (ref "R58")
      (value "1K")
      (footprint "eagle-import:RC0402N_YAG")
      (fields
        (field (name "MANUFACTURER_PART_NUMBER") "RC0402JR-071KL")
        (field (name "COPYRIGHT") "Copyright (C) 2023 Ultra Librarian. All rights reserved.")
      )
      (libsource (lib "eagle-import") (part "RC0402JR-071KLRC0402N_YAG"))
    )
    (comp (ref "R59")
      (value "1K")
      (footprint "eagle-import:RC0402N_YAG")
      (fields
        (field (name "MANUFACTURER_PART_NUMBER") "RC0402JR-071KL")
        (field (name "COPYRIGHT") "Copyright (C) 2023 Ultra Librarian. All rights reserved.")
      )
      (libsource (lib "eagle-import") (part "RC0402JR-071KLRC0402N_YAG"))
    )
    (comp (ref "R60")
      (value "1K")
      (footprint "eagle-import:RC0402N_YAG")
      (fields
        (field (name "MANUFACTURER_PART_NUMBER") "RC0402JR-071KL")
        (field (name "COPYRIGHT") "Copyright (C) 2023 Ultra Librarian. All rights reserved.")
      )
      (libsource (lib "eagle-import") (part "RC0402JR-071KLRC0402N_YAG"))
    )
    (comp (ref "R61")
      (value "1K")
      (footprint "eagle-import:RC0402N_YAG")
      (fields
        (field (name "MANUFACTURER_PART_NUMBER") "RC0402JR-071KL")
        (field (name "COPYRIGHT") "Copyright (C) 2023 Ultra Librarian. All rights reserved.")
      )
      (libsource (lib "eagle-import") (part "RC0402JR-071KLRC0402N_YAG"))
    )
    (comp (ref "R62")
      (value "1K")
      (footprint "eagle-import:RC0402N_YAG")
      (fields
        (field (name "MANUFACTURER_PART_NUMBER") "RC0402JR-071KL")
        (field (name "COPYRIGHT") "Copyright (C) 2023 Ultra Librarian. All rights reserved.")
      )
      (libsource (lib "eagle-import") (part "RC0402JR-071KLRC0402N_YAG"))
    )
    (comp (ref "R63")
      (value "1K")
      (footprint "eagle-import:RC0402N_YAG")
      (fields
        (field (name "MANUFACTURER_PART_NUMBER") "RC0402JR-071KL")
        (field (name "COPYRIGHT") "Copyright (C) 2023 Ultra Librarian. All rights reserved.")
      )
      (libsource (lib "eagle-import") (part "RC0402JR-071KLRC0402N_YAG"))
    )
    (comp (ref "R64")
      (value "1K")
      (footprint "eagle-import:RC0402N_YAG")
      (fields
        (field (name "MANUFACTURER_PART_NUMBER") "RC0402JR-071KL")
        (field (name "COPYRIGHT") "Copyright (C) 2023 Ultra Librarian. All rights reserved.")
      )
      (libsource (lib "eagle-import") (part "RC0402JR-071KLRC0402N_YAG"))
    )
    (comp (ref "R65")
      (value "1K")
      (footprint "eagle-import:RC0402N_YAG")
      (fields
        (field (name "MANUFACTURER_PART_NUMBER") "RC0402JR-071KL")
        (field (name "COPYRIGHT") "Copyright (C) 2023 Ultra Librarian. All rights reserved.")
      )
      (libsource (lib "eagle-import") (part "RC0402JR-071KLRC0402N_YAG"))
    )
    (comp (ref "R66")
      (value "1K")
      (footprint "eagle-import:RC0402N_YAG")
      (fields
        (field (name "MANUFACTURER_PART_NUMBER") "RC0402JR-071KL")
        (field (name "COPYRIGHT") "Copyright (C) 2023 Ultra Librarian. All rights reserved.")
      )
      (libsource (lib "eagle-import") (part "RC0402JR-071KLRC0402N_YAG"))
    )
    (comp (ref "R67")
      (value "1K")
      (footprint "eagle-import:RC0402N_YAG")
      (fields
        (field (name "MANUFACTURER_PART_NUMBER") "RC0402JR-071KL")
        (field (name "COPYRIGHT") "Copyright (C) 2023 Ultra Librarian. All rights reserved.")
      )
      (libsource (lib "eagle-import") (part "RC0402JR-071KLRC0402N_YAG"))
    )
    (comp (ref "R68")
      (value "1K")
      (footprint "eagle-import:RC0402N_YAG")
      (fields
        (field (name "MANUFACTURER_PART_NUMBER") "RC0402JR-071KL")
        (field (name "COPYRIGHT") "Copyright (C) 2023 Ultra Librarian. All rights reserved.")
      )
      (libsource (lib "eagle-import") (part "RC0402JR-071KLRC0402N_YAG"))
    )
    (comp (ref "R69")
      (value "1K")
      (footprint "eagle-import:RC0402N_YAG")
      (fields
        (field (name "MANUFACTURER_PART_NUMBER") "RC0402JR-071KL")
        (field (name "COPYRIGHT") "Copyright (C) 2023 Ultra Librarian. All rights reserved.")
      )
      (libsource (lib "eagle-import") (part "RC0402JR-071KLRC0402N_YAG"))
    )
    (comp (ref "R70")
      (value "1K")
      (footprint "eagle-import:RC0402N_YAG")
      (fields
        (field (name "MANUFACTURER_PART_NUMBER") "RC0402JR-071KL")
        (field (name "COPYRIGHT") "Copyright (C) 2023 Ultra Librarian. All rights reserved.")
      )
      (libsource (lib "eagle-import") (part "RC0402JR-071KLRC0402N_YAG"))
    )
    (comp (ref "R71")
      (value "1K")
      (footprint "eagle-import:RC0402N_YAG")
      (fields
        (field (name "MANUFACTURER_PART_NUMBER") "RC0402JR-071KL")
        (field (name "COPYRIGHT") "Copyright (C) 2023 Ultra Librarian. All rights reserved.")
      )
      (libsource (lib "eagle-import") (part "RC0402JR-071KLRC0402N_YAG"))
    )
    (comp (ref "R72")
      (value "1K")
      (footprint "eagle-import:RC0402N_YAG")
      (fields
        (field (name "MANUFACTURER_PART_NUMBER") "RC0402JR-071KL")
        (field (name "COPYRIGHT") "Copyright (C) 2023 Ultra Librarian. All rights reserved.")
      )
      (libsource (lib "eagle-import") (part "RC0402JR-071KLRC0402N_YAG"))
    )
    (comp (ref "R73")
      (value "1K")
      (footprint "eagle-import:RC0402N_YAG")
      (fields
        (field (name "MANUFACTURER_PART_NUMBER") "RC0402JR-071KL")
        (field (name "COPYRIGHT") "Copyright (C) 2023 Ultra Librarian. All rights reserved.")
      )
      (libsource (lib "eagle-import") (part "RC0402JR-071KLRC0402N_YAG"))
    )
    (comp (ref "R74")
      (value "1K")
      (footprint "eagle-import:RC0402N_YAG")
      (fields
        (field (name "MANUFACTURER_PART_NUMBER") "RC0402JR-071KL")
        (field (name "COPYRIGHT") "Copyright (C) 2023 Ultra Librarian. All rights reserved.")
      )
      (libsource (lib "eagle-import") (part "RC0402JR-071KLRC0402N_YAG"))
    )
    (comp (ref "R75")
      (value "1K")
      (footprint "eagle-import:RC0402N_YAG")
      (fields
        (field (name "MANUFACTURER_PART_NUMBER") "RC0402JR-071KL")
        (field (name "COPYRIGHT") "Copyright (C) 2023 Ultra Librarian. All rights reserved.")
      )
      (libsource (lib "eagle-import") (part "RC0402JR-071KLRC0402N_YAG"))
    )
    (comp (ref "R76")
      (value "1K")
      (footprint "eagle-import:RC0402N_YAG")
      (fields
        (field (name "MANUFACTURER_PART_NUMBER") "RC0402JR-071KL")
        (field (name "COPYRIGHT") "Copyright (C) 2023 Ultra Librarian. All rights reserved.")
      )
      (libsource (lib "eagle-import") (part "RC0402JR-071KLRC0402N_YAG"))
    )
    (comp (ref "R77")
      (value "1K")
      (footprint "eagle-import:RC0402N_YAG")
      (fields
        (field (name "MANUFACTURER_PART_NUMBER") "RC0402JR-071KL")
        (field (name "COPYRIGHT") "Copyright (C) 2023 Ultra Librarian. All rights reserved.")
      )
      (libsource (lib "eagle-import") (part "RC0402JR-071KLRC0402N_YAG"))
    )
    (comp (ref "R78")
      (value "1K")
      (footprint "eagle-import:RC0402N_YAG")
      (fields
        (field (name "MANUFACTURER_PART_NUMBER") "RC0402JR-071KL")
        (field (name "COPYRIGHT") "Copyright (C) 2023 Ultra Librarian. All rights reserved.")
      )
      (libsource (lib "eagle-import") (part "RC0402JR-071KLRC0402N_YAG"))
    )
    (comp (ref "R79")
      (value "1K")
      (footprint "eagle-import:RC0402N_YAG")
      (fields
        (field (name "MANUFACTURER_PART_NUMBER") "RC0402JR-071KL")
        (field (name "COPYRIGHT") "Copyright (C) 2023 Ultra Librarian. All rights reserved.")
      )
      (libsource (lib "eagle-import") (part "RC0402JR-071KLRC0402N_YAG"))
    )
    (comp (ref "R80")
      (value "1K")
      (footprint "eagle-import:RC0402N_YAG")
      (fields
        (field (name "MANUFACTURER_PART_NUMBER") "RC0402JR-071KL")
        (field (name "COPYRIGHT") "Copyright (C) 2023 Ultra Librarian. All rights reserved.")
      )
      (libsource (lib "eagle-import") (part "RC0402JR-071KLRC0402N_YAG"))
    )
    (comp (ref "R81")
      (value "1K")
      (footprint "eagle-import:RC0402N_YAG")
      (fields
        (field (name "MANUFACTURER_PART_NUMBER") "RC0402JR-071KL")
        (field (name "COPYRIGHT") "Copyright (C) 2023 Ultra Librarian. All rights reserved.")
      )
      (libsource (lib "eagle-import") (part "RC0402JR-071KLRC0402N_YAG"))
    )
    (comp (ref "R82")
      (value "1K")
      (footprint "eagle-import:RC0402N_YAG")
      (fields
        (field (name "MANUFACTURER_PART_NUMBER") "RC0402JR-071KL")
        (field (name "COPYRIGHT") "Copyright (C) 2023 Ultra Librarian. All rights reserved.")
      )
      (libsource (lib "eagle-import") (part "RC0402JR-071KLRC0402N_YAG"))
    )
    (comp (ref "R83")
      (value "1K")
      (footprint "eagle-import:RC0402N_YAG")
      (fields
        (field (name "MANUFACTURER_PART_NUMBER") "RC0402JR-071KL")
        (field (name "COPYRIGHT") "Copyright (C) 2023 Ultra Librarian. All rights reserved.")
      )
      (libsource (lib "eagle-import") (part "RC0402JR-071KLRC0402N_YAG"))
    )
    (comp (ref "R84")
      (value "1K")
      (footprint "eagle-import:RC0402N_YAG")
      (fields
        (field (name "MANUFACTURER_PART_NUMBER") "RC0402JR-071KL")
        (field (name "COPYRIGHT") "Copyright (C) 2023 Ultra Librarian. All rights reserved.")
      )
      (libsource (lib "eagle-import") (part "RC0402JR-071KLRC0402N_YAG"))
    )
    (comp (ref "R85")
      (value "1K")
      (footprint "eagle-import:RC0402N_YAG")
      (fields
        (field (name "MANUFACTURER_PART_NUMBER") "RC0402JR-071KL")
        (field (name "COPYRIGHT") "Copyright (C) 2023 Ultra Librarian. All rights reserved.")
      )
      (libsource (lib "eagle-import") (part "RC0402JR-071KLRC0402N_YAG"))
    )
    (comp (ref "R86")
      (value "1K")
      (footprint "eagle-import:RC0402N_YAG")
      (fields
        (field (name "MANUFACTURER_PART_NUMBER") "RC0402JR-071KL")
        (field (name "COPYRIGHT") "Copyright (C) 2023 Ultra Librarian. All rights reserved.")
      )
      (libsource (lib "eagle-import") (part "RC0402JR-071KLRC0402N_YAG"))
    )
    (comp (ref "R87")
      (value "1K")
      (footprint "eagle-import:RC0402N_YAG")
      (fields
        (field (name "MANUFACTURER_PART_NUMBER") "RC0402JR-071KL")
        (field (name "COPYRIGHT") "Copyright (C) 2023 Ultra Librarian. All rights reserved.")
      )
      (libsource (lib "eagle-import") (part "RC0402JR-071KLRC0402N_YAG"))
    )
    (comp (ref "U1")
      (value "TS5A3359DCUR")
      (footprint "eagle-import:SOP50P310X90-8N")
      (libsource (lib "eagle-import") (part "TS5A3359DCUR"))
    )
    (comp (ref "U2")
      (value "TS5A3359DCUR")
      (footprint "eagle-import:SOP50P310X90-8N")
      (libsource (lib "eagle-import") (part "TS5A3359DCUR"))
    )
    (comp (ref "U3")
      (value "TS5A3359DCUR")
      (footprint "eagle-import:SOP50P310X90-8N")
      (libsource (lib "eagle-import") (part "TS5A3359DCUR"))
    )
    (comp (ref "U4")
      (value "TS5A3359DCUR")
      (footprint "eagle-import:SOP50P310X90-8N")
      (libsource (lib "eagle-import") (part "TS5A3359DCUR"))
    )
    (comp (ref "U5")
      (value "TS5A3359DCUR")
      (footprint "eagle-import:SOP50P310X90-8N")
      (libsource (lib "eagle-import") (part "TS5A3359DCUR"))
    )
    (comp (ref "U6")
      (value "TS5A3359DCUR")
      (footprint "eagle-import:SOP50P310X90-8N")
      (libsource (lib "eagle-import") (part "TS5A3359DCUR"))
    )
    (comp (ref "U7")
      (value "TS5A3359DCUR")
      (footprint "eagle-import:SOP50P310X90-8N")
      (libsource (lib "eagle-import") (part "TS5A3359DCUR"))
    )
    (comp (ref "U8")
      (value "TS5A3359DCUR")
      (footprint "eagle-import:SOP50P310X90-8N")
      (libsource (lib "eagle-import") (part "TS5A3359DCUR"))
    )
    (comp (ref "U9")
      (value "TS5A3359DCUR")
      (footprint "eagle-import:SOP50P310X90-8N")
      (libsource (lib "eagle-import") (part "TS5A3359DCUR"))
    )
    (comp (ref "U10")
      (value "TS5A3359DCUR")
      (footprint "eagle-import:SOP50P310X90-8N")
      (libsource (lib "eagle-import") (part "TS5A3359DCUR"))
    )
    (comp (ref "U11")
      (value "TS5A3359DCUR")
      (footprint "eagle-import:SOP50P310X90-8N")
      (libsource (lib "eagle-import") (part "TS5A3359DCUR"))
    )
    (comp (ref "U12")
      (value "TS5A3359DCUR")
      (footprint "eagle-import:SOP50P310X90-8N")
      (libsource (lib "eagle-import") (part "TS5A3359DCUR"))
    )
    (comp (ref "U13")
      (value "TS5A3359DCUR")
      (footprint "eagle-import:SOP50P310X90-8N")
      (libsource (lib "eagle-import") (part "TS5A3359DCUR"))
    )
    (comp (ref "U14")
      (value "TS5A3359DCUR")
      (footprint "eagle-import:SOP50P310X90-8N")
      (libsource (lib "eagle-import") (part "TS5A3359DCUR"))
    )
    (comp (ref "U15")
      (value "TS5A3359DCUR")
      (footprint "eagle-import:SOP50P310X90-8N")
      (libsource (lib "eagle-import") (part "TS5A3359DCUR"))
    )
    (comp (ref "U16")
      (value "TS5A3359DCUR")
      (footprint "eagle-import:SOP50P310X90-8N")
      (libsource (lib "eagle-import") (part "TS5A3359DCUR"))
    )
  )
  (nets
    (net (code "1") (name "+V") (class "Default")
      (node (ref "IC10") (pin "5") (pinfunction "LOAD_-_SWITCH_#2_1_5") (pintype "bidirectional"))
      (node (ref "IC11") (pin "5") (pinfunction "LOAD_-_SWITCH_#2_1_5") (pintype "bidirectional"))
      (node (ref "IC12") (pin "5") (pinfunction "LOAD_-_SWITCH_#2_1_5") (pintype "bidirectional"))
      (node (ref "IC13") (pin "5") (pinfunction "LOAD_-_SWITCH_#2_1_5") (pintype "bidirectional"))
      (node (ref "IC14") (pin "5") (pinfunction "LOAD_-_SWITCH_#2_1_5") (pintype "bidirectional"))
      (node (ref "IC15") (pin "5") (pinfunction "LOAD_-_SWITCH_#2_1_5") (pintype "bidirectional"))
      (node (ref "IC16") (pin "5") (pinfunction "LOAD_-_SWITCH_#2_1_5") (pintype "bidirectional"))
      (node (ref "IC17") (pin "5") (pinfunction "LOAD_-_SWITCH_#2_1_5") (pintype "bidirectional"))
      (node (ref "IC18") (pin "5") (pinfunction "LOAD_-_SWITCH_#2_1_5") (pintype "bidirectional"))
      (node (ref "IC19") (pin "5") (pinfunction "LOAD_-_SWITCH_#2_1_5") (pintype "bidirectional"))
      (node (ref "IC20") (pin "5") (pinfunction "LOAD_-_SWITCH_#2_1_5") (pintype "bidirectional"))
      (node (ref "IC5") (pin "5") (pinfunction "LOAD_-_SWITCH_#2_1_5") (pintype "bidirectional"))
      (node (ref "IC6") (pin "5") (pinfunction "LOAD_-_SWITCH_#2_1_5") (pintype "bidirectional"))
      (node (ref "IC7") (pin "5") (pinfunction "LOAD_-_SWITCH_#2_1_5") (pintype "bidirectional"))
      (node (ref "IC8") (pin "5") (pinfunction "LOAD_-_SWITCH_#2_1_5") (pintype "bidirectional"))
      (node (ref "IC9") (pin "5") (pinfunction "LOAD_-_SWITCH_#2_1_5") (pintype "bidirectional"))
      (node (ref "J6") (pin "5") (pinfunction "5_5") (pintype "bidirectional"))
    )
    (net (code "2") (name "-V") (class "Default")
      (node (ref "IC10") (pin "8") (pinfunction "LOAD_-_SWITCH_#1_2_8") (pintype "bidirectional"))
      (node (ref "IC11") (pin "8") (pinfunction "LOAD_-_SWITCH_#1_2_8") (pintype "bidirectional"))
      (node (ref "IC12") (pin "8") (pinfunction "LOAD_-_SWITCH_#1_2_8") (pintype "bidirectional"))
      (node (ref "IC13") (pin "8") (pinfunction "LOAD_-_SWITCH_#1_2_8") (pintype "bidirectional"))
      (node (ref "IC14") (pin "8") (pinfunction "LOAD_-_SWITCH_#1_2_8") (pintype "bidirectional"))
      (node (ref "IC15") (pin "8") (pinfunction "LOAD_-_SWITCH_#1_2_8") (pintype "bidirectional"))
      (node (ref "IC16") (pin "8") (pinfunction "LOAD_-_SWITCH_#1_2_8") (pintype "bidirectional"))
      (node (ref "IC17") (pin "8") (pinfunction "LOAD_-_SWITCH_#1_2_8") (pintype "bidirectional"))
      (node (ref "IC18") (pin "8") (pinfunction "LOAD_-_SWITCH_#1_2_8") (pintype "bidirectional"))
      (node (ref "IC19") (pin "8") (pinfunction "LOAD_-_SWITCH_#1_2_8") (pintype "bidirectional"))
      (node (ref "IC20") (pin "8") (pinfunction "LOAD_-_SWITCH_#1_2_8") (pintype "bidirectional"))
      (node (ref "IC5") (pin "8") (pinfunction "LOAD_-_SWITCH_#1_2_8") (pintype "bidirectional"))
      (node (ref "IC6") (pin "8") (pinfunction "LOAD_-_SWITCH_#1_2_8") (pintype "bidirectional"))
      (node (ref "IC7") (pin "8") (pinfunction "LOAD_-_SWITCH_#1_2_8") (pintype "bidirectional"))
      (node (ref "IC8") (pin "8") (pinfunction "LOAD_-_SWITCH_#1_2_8") (pintype "bidirectional"))
      (node (ref "IC9") (pin "8") (pinfunction "LOAD_-_SWITCH_#1_2_8") (pintype "bidirectional"))
      (node (ref "J5") (pin "5") (pinfunction "5_5") (pintype "bidirectional"))
    )
    (net (code "3") (name "/2") (class "Default")
      (node (ref "OUTPUT_ENABLE") (pin "2") (pinfunction "2_2") (pintype "passive"))
      (node (ref "R59") (pin "1") (pinfunction "1_1") (pintype "passive"))
    )
    (net (code "4") (name "/3.3V") (class "Default")
      (node (ref "J3") (pin "1") (pinfunction "3.3V_1") (pintype "power_in"))
      (node (ref "J3") (pin "17") (pinfunction "3.3V_17") (pintype "power_in"))
      (node (ref "JP4") (pin "33") (pinfunction "33_33") (pintype "passive"))
      (node (ref "JP4") (pin "35") (pinfunction "35_35") (pintype "passive"))
    )
    (net (code "5") (name "/A-CTRL1") (class "Default")
      (node (ref "R6") (pin "2") (pinfunction "2_2") (pintype "passive"))
      (node (ref "U1") (pin "2") (pinfunction "NO1_2") (pintype "bidirectional"))
    )
    (net (code "6") (name "/A-CTRL2") (class "Default")
      (node (ref "R8") (pin "2") (pinfunction "2_2") (pintype "passive"))
      (node (ref "U2") (pin "2") (pinfunction "NO1_2") (pintype "bidirectional"))
    )
    (net (code "7") (name "/A-CTRL3") (class "Default")
      (node (ref "R10") (pin "2") (pinfunction "2_2") (pintype "passive"))
      (node (ref "U3") (pin "2") (pinfunction "NO1_2") (pintype "bidirectional"))
    )
    (net (code "8") (name "/A-CTRL4") (class "Default")
      (node (ref "R12") (pin "2") (pinfunction "2_2") (pintype "passive"))
      (node (ref "U4") (pin "2") (pinfunction "NO1_2") (pintype "bidirectional"))
    )
    (net (code "9") (name "/A-CTRL5") (class "Default")
      (node (ref "R14") (pin "2") (pinfunction "2_2") (pintype "passive"))
      (node (ref "U5") (pin "2") (pinfunction "NO1_2") (pintype "bidirectional"))
    )
    (net (code "10") (name "/A-CTRL6") (class "Default")
      (node (ref "R16") (pin "2") (pinfunction "2_2") (pintype "passive"))
      (node (ref "U6") (pin "2") (pinfunction "NO1_2") (pintype "bidirectional"))
    )
    (net (code "11") (name "/A-CTRL7") (class "Default")
      (node (ref "R18") (pin "2") (pinfunction "2_2") (pintype "passive"))
      (node (ref "U7") (pin "2") (pinfunction "NO1_2") (pintype "bidirectional"))
    )
    (net (code "12") (name "/A-CTRL8") (class "Default")
      (node (ref "R20") (pin "2") (pinfunction "2_2") (pintype "passive"))
      (node (ref "U8") (pin "2") (pinfunction "NO1_2") (pintype "bidirectional"))
    )
    (net (code "13") (name "/A-CTRL9") (class "Default")
      (node (ref "R38") (pin "2") (pinfunction "2_2") (pintype "passive"))
      (node (ref "U9") (pin "2") (pinfunction "NO1_2") (pintype "bidirectional"))
    )
    (net (code "14") (name "/A-CTRL10") (class "Default")
      (node (ref "R40") (pin "2") (pinfunction "2_2") (pintype "passive"))
      (node (ref "U10") (pin "2") (pinfunction "NO1_2") (pintype "bidirectional"))
    )
    (net (code "15") (name "/A-CTRL11") (class "Default")
      (node (ref "R42") (pin "2") (pinfunction "2_2") (pintype "passive"))
      (node (ref "U11") (pin "2") (pinfunction "NO1_2") (pintype "bidirectional"))
    )
    (net (code "16") (name "/A-CTRL12") (class "Default")
      (node (ref "R44") (pin "2") (pinfunction "2_2") (pintype "passive"))
      (node (ref "U12") (pin "2") (pinfunction "NO1_2") (pintype "bidirectional"))
    )
    (net (code "17") (name "/A-CTRL13") (class "Default")
      (node (ref "R46") (pin "2") (pinfunction "2_2") (pintype "passive"))
      (node (ref "U13") (pin "2") (pinfunction "NO1_2") (pintype "bidirectional"))
    )
    (net (code "18") (name "/A-CTRL14") (class "Default")
      (node (ref "R48") (pin "2") (pinfunction "2_2") (pintype "passive"))
      (node (ref "U14") (pin "2") (pinfunction "NO1_2") (pintype "bidirectional"))
    )
    (net (code "19") (name "/A-CTRL15") (class "Default")
      (node (ref "R50") (pin "2") (pinfunction "2_2") (pintype "passive"))
      (node (ref "U15") (pin "2") (pinfunction "NO1_2") (pintype "bidirectional"))
    )
    (net (code "20") (name "/A-CTRL16") (class "Default")
      (node (ref "R52") (pin "2") (pinfunction "2_2") (pintype "passive"))
      (node (ref "U16") (pin "2") (pinfunction "NO1_2") (pintype "bidirectional"))
    )
    (net (code "21") (name "/C-CTRL1") (class "Default")
      (node (ref "R7") (pin "2") (pinfunction "2_2") (pintype "passive"))
      (node (ref "U1") (pin "1") (pinfunction "NOO_1") (pintype "bidirectional"))
    )
    (net (code "22") (name "/C-CTRL2") (class "Default")
      (node (ref "R9") (pin "2") (pinfunction "2_2") (pintype "passive"))
      (node (ref "U2") (pin "1") (pinfunction "NOO_1") (pintype "bidirectional"))
    )
    (net (code "23") (name "/C-CTRL3") (class "Default")
      (node (ref "R11") (pin "2") (pinfunction "2_2") (pintype "passive"))
      (node (ref "U3") (pin "1") (pinfunction "NOO_1") (pintype "bidirectional"))
    )
    (net (code "24") (name "/C-CTRL4") (class "Default")
      (node (ref "R13") (pin "2") (pinfunction "2_2") (pintype "passive"))
      (node (ref "U4") (pin "1") (pinfunction "NOO_1") (pintype "bidirectional"))
    )
    (net (code "25") (name "/C-CTRL5") (class "Default")
      (node (ref "R15") (pin "2") (pinfunction "2_2") (pintype "passive"))
      (node (ref "U5") (pin "1") (pinfunction "NOO_1") (pintype "bidirectional"))
    )
    (net (code "26") (name "/C-CTRL6") (class "Default")
      (node (ref "R17") (pin "2") (pinfunction "2_2") (pintype "passive"))
      (node (ref "U6") (pin "1") (pinfunction "NOO_1") (pintype "bidirectional"))
    )
    (net (code "27") (name "/C-CTRL7") (class "Default")
      (node (ref "R19") (pin "2") (pinfunction "2_2") (pintype "passive"))
      (node (ref "U7") (pin "1") (pinfunction "NOO_1") (pintype "bidirectional"))
    )
    (net (code "28") (name "/C-CTRL8") (class "Default")
      (node (ref "R21") (pin "2") (pinfunction "2_2") (pintype "passive"))
      (node (ref "U8") (pin "1") (pinfunction "NOO_1") (pintype "bidirectional"))
    )
    (net (code "29") (name "/C-CTRL9") (class "Default")
      (node (ref "R39") (pin "2") (pinfunction "2_2") (pintype "passive"))
      (node (ref "U9") (pin "1") (pinfunction "NOO_1") (pintype "bidirectional"))
    )
    (net (code "30") (name "/C-CTRL10") (class "Default")
      (node (ref "R41") (pin "2") (pinfunction "2_2") (pintype "passive"))
      (node (ref "U10") (pin "1") (pinfunction "NOO_1") (pintype "bidirectional"))
    )
    (net (code "31") (name "/C-CTRL11") (class "Default")
      (node (ref "R43") (pin "2") (pinfunction "2_2") (pintype "passive"))
      (node (ref "U11") (pin "1") (pinfunction "NOO_1") (pintype "bidirectional"))
    )
    (net (code "32") (name "/C-CTRL12") (class "Default")
      (node (ref "R45") (pin "2") (pinfunction "2_2") (pintype "passive"))
      (node (ref "U12") (pin "1") (pinfunction "NOO_1") (pintype "bidirectional"))
    )
    (net (code "33") (name "/C-CTRL13") (class "Default")
      (node (ref "R47") (pin "2") (pinfunction "2_2") (pintype "passive"))
      (node (ref "U13") (pin "1") (pinfunction "NOO_1") (pintype "bidirectional"))
    )
    (net (code "34") (name "/C-CTRL14") (class "Default")
      (node (ref "R49") (pin "2") (pinfunction "2_2") (pintype "passive"))
      (node (ref "U14") (pin "1") (pinfunction "NOO_1") (pintype "bidirectional"))
    )
    (net (code "35") (name "/C-CTRL15") (class "Default")
      (node (ref "R51") (pin "2") (pinfunction "2_2") (pintype "passive"))
      (node (ref "U15") (pin "1") (pinfunction "NOO_1") (pintype "bidirectional"))
    )
    (net (code "36") (name "/C-CTRL16") (class "Default")
      (node (ref "R53") (pin "2") (pinfunction "2_2") (pintype "passive"))
      (node (ref "U16") (pin "1") (pinfunction "NOO_1") (pintype "bidirectional"))
    )
    (net (code "37") (name "/CE0") (class "Default")
      (node (ref "J3") (pin "24") (pinfunction "CE0_24") (pintype "output"))
      (node (ref "JP4") (pin "25") (pinfunction "25_25") (pintype "passive"))
    )
    (net (code "38") (name "/CE1") (class "Default")
      (node (ref "J3") (pin "26") (pinfunction "CE1_26") (pintype "output"))
      (node (ref "JP4") (pin "27") (pinfunction "27_27") (pintype "passive"))
    )
    (net (code "39") (name "/ESP1") (class "Default")
      (node (ref "IC21") (pin "7") (pinfunction "LOAD_-_SWITCH_#1_1_7") (pintype "bidirectional"))
      (node (ref "IC5") (pin "6") (pinfunction "LOAD_-_SWITCH_#2_2_6") (pintype "bidirectional"))
      (node (ref "IC5") (pin "7") (pinfunction "LOAD_-_SWITCH_#1_1_7") (pintype "bidirectional"))
      (node (ref "J4") (pin "02") (pinfunction "02_02") (pintype "passive"))
    )
    (net (code "40") (name "/ESP2") (class "Default")
      (node (ref "IC21") (pin "6") (pinfunction "LOAD_-_SWITCH_#2_2_6") (pintype "bidirectional"))
      (node (ref "IC6") (pin "6") (pinfunction "LOAD_-_SWITCH_#2_2_6") (pintype "bidirectional"))
      (node (ref "IC6") (pin "7") (pinfunction "LOAD_-_SWITCH_#1_1_7") (pintype "bidirectional"))
      (node (ref "J4") (pin "04") (pinfunction "04_04") (pintype "passive"))
    )
    (net (code "41") (name "/ESP3") (class "Default")
      (node (ref "IC22") (pin "7") (pinfunction "LOAD_-_SWITCH_#1_1_7") (pintype "bidirectional"))
      (node (ref "IC7") (pin "6") (pinfunction "LOAD_-_SWITCH_#2_2_6") (pintype "bidirectional"))
      (node (ref "IC7") (pin "7") (pinfunction "LOAD_-_SWITCH_#1_1_7") (pintype "bidirectional"))
      (node (ref "J4") (pin "06") (pinfunction "06_06") (pintype "passive"))
    )
    (net (code "42") (name "/ESP4") (class "Default")
      (node (ref "IC22") (pin "6") (pinfunction "LOAD_-_SWITCH_#2_2_6") (pintype "bidirectional"))
      (node (ref "IC8") (pin "6") (pinfunction "LOAD_-_SWITCH_#2_2_6") (pintype "bidirectional"))
      (node (ref "IC8") (pin "7") (pinfunction "LOAD_-_SWITCH_#1_1_7") (pintype "bidirectional"))
      (node (ref "J4") (pin "08") (pinfunction "08_08") (pintype "passive"))
    )
    (net (code "43") (name "/ESP5") (class "Default")
      (node (ref "IC23") (pin "7") (pinfunction "LOAD_-_SWITCH_#1_1_7") (pintype "bidirectional"))
      (node (ref "IC9") (pin "6") (pinfunction "LOAD_-_SWITCH_#2_2_6") (pintype "bidirectional"))
      (node (ref "IC9") (pin "7") (pinfunction "LOAD_-_SWITCH_#1_1_7") (pintype "bidirectional"))
      (node (ref "J4") (pin "10") (pinfunction "10_10") (pintype "passive"))
    )
    (net (code "44") (name "/ESP6") (class "Default")
      (node (ref "IC10") (pin "6") (pinfunction "LOAD_-_SWITCH_#2_2_6") (pintype "bidirectional"))
      (node (ref "IC10") (pin "7") (pinfunction "LOAD_-_SWITCH_#1_1_7") (pintype "bidirectional"))
      (node (ref "IC23") (pin "6") (pinfunction "LOAD_-_SWITCH_#2_2_6") (pintype "bidirectional"))
      (node (ref "J4") (pin "12") (pinfunction "12_12") (pintype "passive"))
    )
    (net (code "45") (name "/ESP7") (class "Default")
      (node (ref "IC11") (pin "6") (pinfunction "LOAD_-_SWITCH_#2_2_6") (pintype "bidirectional"))
      (node (ref "IC11") (pin "7") (pinfunction "LOAD_-_SWITCH_#1_1_7") (pintype "bidirectional"))
      (node (ref "IC24") (pin "7") (pinfunction "LOAD_-_SWITCH_#1_1_7") (pintype "bidirectional"))
      (node (ref "J4") (pin "14") (pinfunction "14_14") (pintype "passive"))
    )
    (net (code "46") (name "/ESP8") (class "Default")
      (node (ref "IC12") (pin "6") (pinfunction "LOAD_-_SWITCH_#2_2_6") (pintype "bidirectional"))
      (node (ref "IC12") (pin "7") (pinfunction "LOAD_-_SWITCH_#1_1_7") (pintype "bidirectional"))
      (node (ref "IC24") (pin "6") (pinfunction "LOAD_-_SWITCH_#2_2_6") (pintype "bidirectional"))
      (node (ref "J4") (pin "16") (pinfunction "16_16") (pintype "passive"))
    )
    (net (code "47") (name "/ESP9") (class "Default")
      (node (ref "IC13") (pin "6") (pinfunction "LOAD_-_SWITCH_#2_2_6") (pintype "bidirectional"))
      (node (ref "IC13") (pin "7") (pinfunction "LOAD_-_SWITCH_#1_1_7") (pintype "bidirectional"))
      (node (ref "IC25") (pin "7") (pinfunction "LOAD_-_SWITCH_#1_1_7") (pintype "bidirectional"))
      (node (ref "J7") (pin "02") (pinfunction "02_02") (pintype "passive"))
    )
    (net (code "48") (name "/ESP10") (class "Default")
      (node (ref "IC14") (pin "6") (pinfunction "LOAD_-_SWITCH_#2_2_6") (pintype "bidirectional"))
      (node (ref "IC14") (pin "7") (pinfunction "LOAD_-_SWITCH_#1_1_7") (pintype "bidirectional"))
      (node (ref "IC25") (pin "6") (pinfunction "LOAD_-_SWITCH_#2_2_6") (pintype "bidirectional"))
      (node (ref "J7") (pin "04") (pinfunction "04_04") (pintype "passive"))
    )
    (net (code "49") (name "/ESP11") (class "Default")
      (node (ref "IC15") (pin "6") (pinfunction "LOAD_-_SWITCH_#2_2_6") (pintype "bidirectional"))
      (node (ref "IC15") (pin "7") (pinfunction "LOAD_-_SWITCH_#1_1_7") (pintype "bidirectional"))
      (node (ref "IC26") (pin "7") (pinfunction "LOAD_-_SWITCH_#1_1_7") (pintype "bidirectional"))
      (node (ref "J7") (pin "06") (pinfunction "06_06") (pintype "passive"))
    )
    (net (code "50") (name "/ESP12") (class "Default")
      (node (ref "IC16") (pin "6") (pinfunction "LOAD_-_SWITCH_#2_2_6") (pintype "bidirectional"))
      (node (ref "IC16") (pin "7") (pinfunction "LOAD_-_SWITCH_#1_1_7") (pintype "bidirectional"))
      (node (ref "IC26") (pin "6") (pinfunction "LOAD_-_SWITCH_#2_2_6") (pintype "bidirectional"))
      (node (ref "J7") (pin "08") (pinfunction "08_08") (pintype "passive"))
    )
    (net (code "51") (name "/ESP13") (class "Default")
      (node (ref "IC17") (pin "6") (pinfunction "LOAD_-_SWITCH_#2_2_6") (pintype "bidirectional"))
      (node (ref "IC17") (pin "7") (pinfunction "LOAD_-_SWITCH_#1_1_7") (pintype "bidirectional"))
      (node (ref "IC27") (pin "7") (pinfunction "LOAD_-_SWITCH_#1_1_7") (pintype "bidirectional"))
      (node (ref "J7") (pin "10") (pinfunction "10_10") (pintype "passive"))
    )
    (net (code "52") (name "/ESP14") (class "Default")
      (node (ref "IC18") (pin "6") (pinfunction "LOAD_-_SWITCH_#2_2_6") (pintype "bidirectional"))
      (node (ref "IC18") (pin "7") (pinfunction "LOAD_-_SWITCH_#1_1_7") (pintype "bidirectional"))
      (node (ref "IC27") (pin "6") (pinfunction "LOAD_-_SWITCH_#2_2_6") (pintype "bidirectional"))
      (node (ref "J7") (pin "12") (pinfunction "12_12") (pintype "passive"))
    )
    (net (code "53") (name "/ESP15") (class "Default")
      (node (ref "IC19") (pin "6") (pinfunction "LOAD_-_SWITCH_#2_2_6") (pintype "bidirectional"))
      (node (ref "IC19") (pin "7") (pinfunction "LOAD_-_SWITCH_#1_1_7") (pintype "bidirectional"))
      (node (ref "IC28") (pin "7") (pinfunction "LOAD_-_SWITCH_#1_1_7") (pintype "bidirectional"))
      (node (ref "J7") (pin "14") (pinfunction "14_14") (pintype "passive"))
    )
    (net (code "54") (name "/ESP16") (class "Default")
      (node (ref "IC20") (pin "6") (pinfunction "LOAD_-_SWITCH_#2_2_6") (pintype "bidirectional"))
      (node (ref "IC20") (pin "7") (pinfunction "LOAD_-_SWITCH_#1_1_7") (pintype "bidirectional"))
      (node (ref "IC28") (pin "6") (pinfunction "LOAD_-_SWITCH_#2_2_6") (pintype "bidirectional"))
      (node (ref "J7") (pin "16") (pinfunction "16_16") (pintype "passive"))
    )
    (net (code "55") (name "/GND-CTRL1") (class "Default")
      (node (ref "R22") (pin "2") (pinfunction "2_2") (pintype "passive"))
      (node (ref "U1") (pin "3") (pinfunction "NOZ_3") (pintype "bidirectional"))
    )
    (net (code "56") (name "/GND-CTRL2") (class "Default")
      (node (ref "R23") (pin "2") (pinfunction "2_2") (pintype "passive"))
      (node (ref "U2") (pin "3") (pinfunction "NOZ_3") (pintype "bidirectional"))
    )
    (net (code "57") (name "/GND-CTRL3") (class "Default")
      (node (ref "R24") (pin "2") (pinfunction "2_2") (pintype "passive"))
      (node (ref "U3") (pin "3") (pinfunction "NOZ_3") (pintype "bidirectional"))
    )
    (net (code "58") (name "/GND-CTRL4") (class "Default")
      (node (ref "R25") (pin "2") (pinfunction "2_2") (pintype "passive"))
      (node (ref "U4") (pin "3") (pinfunction "NOZ_3") (pintype "bidirectional"))
    )
    (net (code "59") (name "/GND-CTRL5") (class "Default")
      (node (ref "R26") (pin "2") (pinfunction "2_2") (pintype "passive"))
      (node (ref "U5") (pin "3") (pinfunction "NOZ_3") (pintype "bidirectional"))
    )
    (net (code "60") (name "/GND-CTRL6") (class "Default")
      (node (ref "R27") (pin "2") (pinfunction "2_2") (pintype "passive"))
      (node (ref "U6") (pin "3") (pinfunction "NOZ_3") (pintype "bidirectional"))
    )
    (net (code "61") (name "/GND-CTRL7") (class "Default")
      (node (ref "R28") (pin "2") (pinfunction "2_2") (pintype "passive"))
      (node (ref "U7") (pin "3") (pinfunction "NOZ_3") (pintype "bidirectional"))
    )
    (net (code "62") (name "/GND-CTRL8") (class "Default")
      (node (ref "R29") (pin "2") (pinfunction "2_2") (pintype "passive"))
      (node (ref "U8") (pin "3") (pinfunction "NOZ_3") (pintype "bidirectional"))
    )
    (net (code "63") (name "/GND-CTRL9") (class "Default")
      (node (ref "R30") (pin "2") (pinfunction "2_2") (pintype "passive"))
      (node (ref "U9") (pin "3") (pinfunction "NOZ_3") (pintype "bidirectional"))
    )
    (net (code "64") (name "/GND-CTRL10") (class "Default")
      (node (ref "R31") (pin "2") (pinfunction "2_2") (pintype "passive"))
      (node (ref "U10") (pin "3") (pinfunction "NOZ_3") (pintype "bidirectional"))
    )
    (net (code "65") (name "/GND-CTRL11") (class "Default")
      (node (ref "R32") (pin "2") (pinfunction "2_2") (pintype "passive"))
      (node (ref "U11") (pin "3") (pinfunction "NOZ_3") (pintype "bidirectional"))
    )
    (net (code "66") (name "/GND-CTRL12") (class "Default")
      (node (ref "R33") (pin "2") (pinfunction "2_2") (pintype "passive"))
      (node (ref "U12") (pin "3") (pinfunction "NOZ_3") (pintype "bidirectional"))
    )
    (net (code "67") (name "/GND-CTRL13") (class "Default")
      (node (ref "R34") (pin "2") (pinfunction "2_2") (pintype "passive"))
      (node (ref "U13") (pin "3") (pinfunction "NOZ_3") (pintype "bidirectional"))
    )
    (net (code "68") (name "/GND-CTRL14") (class "Default")
      (node (ref "R35") (pin "2") (pinfunction "2_2") (pintype "passive"))
      (node (ref "U14") (pin "3") (pinfunction "NOZ_3") (pintype "bidirectional"))
    )
    (net (code "69") (name "/GND-CTRL15") (class "Default")
      (node (ref "R36") (pin "2") (pinfunction "2_2") (pintype "passive"))
      (node (ref "U15") (pin "3") (pinfunction "NOZ_3") (pintype "bidirectional"))
    )
    (net (code "70") (name "/GND-CTRL16") (class "Default")
      (node (ref "R37") (pin "2") (pinfunction "2_2") (pintype "passive"))
      (node (ref "U16") (pin "3") (pinfunction "NOZ_3") (pintype "bidirectional"))
    )
    (net (code "71") (name "/GP4") (class "Default")
      (node (ref "J3") (pin "7") (pinfunction "GP4_7") (pintype "bidirectional"))
      (node (ref "JP4") (pin "3") (pinfunction "3_3") (pintype "passive"))
    )
    (net (code "72") (name "/GP5") (class "Default")
      (node (ref "IC1") (pin "3") (pinfunction "D0_3") (pintype "bidirectional"))
      (node (ref "IC2") (pin "3") (pinfunction "D0_3") (pintype "bidirectional"))
      (node (ref "IC3") (pin "3") (pinfunction "D0_3") (pintype "bidirectional"))
      (node (ref "IC4") (pin "3") (pinfunction "D0_3") (pintype "bidirectional"))
      (node (ref "J3") (pin "29") (pinfunction "GP5_29") (pintype "bidirectional"))
    )
    (net (code "73") (name "/GP6") (class "Default")
      (node (ref "IC1") (pin "4") (pinfunction "D1_4") (pintype "bidirectional"))
      (node (ref "IC2") (pin "4") (pinfunction "D1_4") (pintype "bidirectional"))
      (node (ref "IC3") (pin "4") (pinfunction "D1_4") (pintype "bidirectional"))
      (node (ref "IC4") (pin "4") (pinfunction "D1_4") (pintype "bidirectional"))
      (node (ref "J3") (pin "31") (pinfunction "GP6_31") (pintype "bidirectional"))
    )
    (net (code "74") (name "/GP12") (class "Default")
      (node (ref "IC1") (pin "7") (pinfunction "D2_7") (pintype "bidirectional"))
      (node (ref "IC2") (pin "7") (pinfunction "D2_7") (pintype "bidirectional"))
      (node (ref "IC3") (pin "7") (pinfunction "D2_7") (pintype "bidirectional"))
      (node (ref "IC4") (pin "7") (pinfunction "D2_7") (pintype "bidirectional"))
      (node (ref "J3") (pin "32") (pinfunction "GP12_32") (pintype "bidirectional"))
    )
    (net (code "75") (name "/GP13") (class "Default")
      (node (ref "IC1") (pin "8") (pinfunction "D3_8") (pintype "bidirectional"))
      (node (ref "IC2") (pin "8") (pinfunction "D3_8") (pintype "bidirectional"))
      (node (ref "IC3") (pin "8") (pinfunction "D3_8") (pintype "bidirectional"))
      (node (ref "IC4") (pin "8") (pinfunction "D3_8") (pintype "bidirectional"))
      (node (ref "J3") (pin "33") (pinfunction "GP13_33") (pintype "bidirectional"))
    )
    (net (code "76") (name "/GP16") (class "Default")
      (node (ref "IC1") (pin "13") (pinfunction "D4_13") (pintype "bidirectional"))
      (node (ref "IC2") (pin "13") (pinfunction "D4_13") (pintype "bidirectional"))
      (node (ref "IC3") (pin "13") (pinfunction "D4_13") (pintype "bidirectional"))
      (node (ref "IC4") (pin "13") (pinfunction "D4_13") (pintype "bidirectional"))
      (node (ref "J3") (pin "36") (pinfunction "GP16_36") (pintype "bidirectional"))
    )
    (net (code "77") (name "/GP17") (class "Default")
      (node (ref "IC1") (pin "14") (pinfunction "D5_14") (pintype "bidirectional"))
      (node (ref "IC2") (pin "14") (pinfunction "D5_14") (pintype "bidirectional"))
      (node (ref "IC3") (pin "14") (pinfunction "D5_14") (pintype "bidirectional"))
      (node (ref "IC4") (pin "14") (pinfunction "D5_14") (pintype "bidirectional"))
      (node (ref "J3") (pin "11") (pinfunction "GP17_11") (pintype "bidirectional"))
    )
    (net (code "78") (name "/GP18#") (class "Default")
      (node (ref "J3") (pin "12") (pinfunction "GP18#_12") (pintype "bidirectional"))
      (node (ref "JP4") (pin "5") (pinfunction "5_5") (pintype "passive"))
    )
    (net (code "79") (name "/GP19") (class "Default")
      (node (ref "IC1") (pin "17") (pinfunction "D6_17") (pintype "bidirectional"))
      (node (ref "IC2") (pin "17") (pinfunction "D6_17") (pintype "bidirectional"))
      (node (ref "IC3") (pin "17") (pinfunction "D6_17") (pintype "bidirectional"))
      (node (ref "IC4") (pin "17") (pinfunction "D6_17") (pintype "bidirectional"))
      (node (ref "J3") (pin "35") (pinfunction "GP19_35") (pintype "bidirectional"))
    )
    (net (code "80") (name "/GP20") (class "Default")
      (node (ref "J3") (pin "38") (pinfunction "GP20_38") (pintype "bidirectional"))
      (node (ref "JP4") (pin "7") (pinfunction "7_7") (pintype "passive"))
    )
    (net (code "81") (name "/GP21") (class "Default")
      (node (ref "J3") (pin "40") (pinfunction "GP21_40") (pintype "bidirectional"))
      (node (ref "JP4") (pin "9") (pinfunction "9_9") (pintype "passive"))
    )
    (net (code "82") (name "/GP26") (class "Default")
      (node (ref "IC1") (pin "18") (pinfunction "D7_18") (pintype "bidirectional"))
      (node (ref "IC2") (pin "18") (pinfunction "D7_18") (pintype "bidirectional"))
      (node (ref "IC3") (pin "18") (pinfunction "D7_18") (pintype "bidirectional"))
      (node (ref "IC4") (pin "18") (pinfunction "D7_18") (pintype "bidirectional"))
      (node (ref "J3") (pin "37") (pinfunction "GP26_37") (pintype "bidirectional"))
    )
    (net (code "83") (name "/ID_SC") (class "Default")
      (node (ref "J3") (pin "28") (pinfunction "ID_SC_28") (pintype "bidirectional"))
      (node (ref "JP4") (pin "31") (pinfunction "31_31") (pintype "passive"))
    )
    (net (code "84") (name "/ID_SD") (class "Default")
      (node (ref "J3") (pin "27") (pinfunction "ID_SD_27") (pintype "bidirectional"))
      (node (ref "JP4") (pin "29") (pinfunction "29_29") (pintype "passive"))
    )
    (net (code "85") (name "/LE1") (class "Default")
      (node (ref "IC1") (pin "11") (pinfunction "LE_11") (pintype "bidirectional"))
      (node (ref "J3") (pin "16") (pinfunction "GP23_16") (pintype "bidirectional"))
      (node (ref "R1") (pin "2") (pinfunction "2_2") (pintype "passive"))
    )
    (net (code "86") (name "/LE2") (class "Default")
      (node (ref "IC2") (pin "11") (pinfunction "LE_11") (pintype "bidirectional"))
      (node (ref "J3") (pin "18") (pinfunction "GP24_18") (pintype "bidirectional"))
      (node (ref "R2") (pin "2") (pinfunction "2_2") (pintype "passive"))
    )
    (net (code "87") (name "/LE3") (class "Default")
      (node (ref "IC3") (pin "11") (pinfunction "LE_11") (pintype "bidirectional"))
      (node (ref "J3") (pin "22") (pinfunction "GP25_22") (pintype "bidirectional"))
      (node (ref "R3") (pin "2") (pinfunction "2_2") (pintype "passive"))
    )
    (net (code "88") (name "/LE4") (class "Default")
      (node (ref "IC4") (pin "11") (pinfunction "LE_11") (pintype "bidirectional"))
      (node (ref "J3") (pin "13") (pinfunction "GP27_13") (pintype "bidirectional"))
      (node (ref "R4") (pin "2") (pinfunction "2_2") (pintype "passive"))
    )
    (net (code "89") (name "/MISO") (class "Default")
      (node (ref "J3") (pin "21") (pinfunction "MISO_21") (pintype "input"))
      (node (ref "JP4") (pin "21") (pinfunction "21_21") (pintype "passive"))
    )
    (net (code "90") (name "/MOSI") (class "Default")
      (node (ref "J3") (pin "19") (pinfunction "MOSI_19") (pintype "output"))
      (node (ref "JP4") (pin "23") (pinfunction "23_23") (pintype "passive"))
    )
    (net (code "91") (name "/O1") (class "Default")
      (node (ref "IC1") (pin "2") (pinfunction "O0_2") (pintype "bidirectional"))
      (node (ref "R55") (pin "2") (pinfunction "2_2") (pintype "passive"))
      (node (ref "U1") (pin "6") (pinfunction "IN1_6") (pintype "input"))
    )
    (net (code "92") (name "/O2") (class "Default")
      (node (ref "IC1") (pin "5") (pinfunction "O1_5") (pintype "bidirectional"))
      (node (ref "R56") (pin "2") (pinfunction "2_2") (pintype "passive"))
      (node (ref "U1") (pin "5") (pinfunction "IN2_5") (pintype "input"))
    )
    (net (code "93") (name "/O3") (class "Default")
      (node (ref "IC1") (pin "6") (pinfunction "O2_6") (pintype "bidirectional"))
      (node (ref "R57") (pin "2") (pinfunction "2_2") (pintype "passive"))
      (node (ref "U2") (pin "6") (pinfunction "IN1_6") (pintype "input"))
    )
    (net (code "94") (name "/O4") (class "Default")
      (node (ref "IC1") (pin "9") (pinfunction "O3_9") (pintype "bidirectional"))
      (node (ref "R58") (pin "2") (pinfunction "2_2") (pintype "passive"))
      (node (ref "U2") (pin "5") (pinfunction "IN2_5") (pintype "input"))
    )
    (net (code "95") (name "/O5") (class "Default")
      (node (ref "IC1") (pin "12") (pinfunction "O4_12") (pintype "bidirectional"))
      (node (ref "R60") (pin "2") (pinfunction "2_2") (pintype "passive"))
      (node (ref "U3") (pin "6") (pinfunction "IN1_6") (pintype "input"))
    )
    (net (code "96") (name "/O6") (class "Default")
      (node (ref "IC1") (pin "15") (pinfunction "O5_15") (pintype "bidirectional"))
      (node (ref "R61") (pin "2") (pinfunction "2_2") (pintype "passive"))
      (node (ref "U3") (pin "5") (pinfunction "IN2_5") (pintype "input"))
    )
    (net (code "97") (name "/O7") (class "Default")
      (node (ref "IC1") (pin "16") (pinfunction "O6_16") (pintype "bidirectional"))
      (node (ref "R62") (pin "2") (pinfunction "2_2") (pintype "passive"))
      (node (ref "U4") (pin "6") (pinfunction "IN1_6") (pintype "input"))
    )
    (net (code "98") (name "/O8") (class "Default")
      (node (ref "IC1") (pin "19") (pinfunction "O7_19") (pintype "bidirectional"))
      (node (ref "R63") (pin "2") (pinfunction "2_2") (pintype "passive"))
      (node (ref "U4") (pin "5") (pinfunction "IN2_5") (pintype "input"))
    )
    (net (code "99") (name "/O9") (class "Default")
      (node (ref "IC2") (pin "2") (pinfunction "O0_2") (pintype "bidirectional"))
      (node (ref "R64") (pin "2") (pinfunction "2_2") (pintype "passive"))
      (node (ref "U5") (pin "6") (pinfunction "IN1_6") (pintype "input"))
    )
    (net (code "100") (name "/O10") (class "Default")
      (node (ref "IC2") (pin "5") (pinfunction "O1_5") (pintype "bidirectional"))
      (node (ref "R65") (pin "2") (pinfunction "2_2") (pintype "passive"))
      (node (ref "U5") (pin "5") (pinfunction "IN2_5") (pintype "input"))
    )
    (net (code "101") (name "/O11") (class "Default")
      (node (ref "IC2") (pin "6") (pinfunction "O2_6") (pintype "bidirectional"))
      (node (ref "R66") (pin "2") (pinfunction "2_2") (pintype "passive"))
      (node (ref "U6") (pin "6") (pinfunction "IN1_6") (pintype "input"))
    )
    (net (code "102") (name "/O12") (class "Default")
      (node (ref "IC2") (pin "9") (pinfunction "O3_9") (pintype "bidirectional"))
      (node (ref "R67") (pin "2") (pinfunction "2_2") (pintype "passive"))
      (node (ref "U6") (pin "5") (pinfunction "IN2_5") (pintype "input"))
    )
    (net (code "103") (name "/O13") (class "Default")
      (node (ref "IC2") (pin "12") (pinfunction "O4_12") (pintype "bidirectional"))
      (node (ref "R68") (pin "2") (pinfunction "2_2") (pintype "passive"))
      (node (ref "U7") (pin "6") (pinfunction "IN1_6") (pintype "input"))
    )
    (net (code "104") (name "/O14") (class "Default")
      (node (ref "IC2") (pin "15") (pinfunction "O5_15") (pintype "bidirectional"))
      (node (ref "R69") (pin "2") (pinfunction "2_2") (pintype "passive"))
      (node (ref "U7") (pin "5") (pinfunction "IN2_5") (pintype "input"))
    )
    (net (code "105") (name "/O15") (class "Default")
      (node (ref "IC2") (pin "16") (pinfunction "O6_16") (pintype "bidirectional"))
      (node (ref "R70") (pin "2") (pinfunction "2_2") (pintype "passive"))
      (node (ref "U8") (pin "6") (pinfunction "IN1_6") (pintype "input"))
    )
    (net (code "106") (name "/O16") (class "Default")
      (node (ref "IC2") (pin "19") (pinfunction "O7_19") (pintype "bidirectional"))
      (node (ref "R71") (pin "2") (pinfunction "2_2") (pintype "passive"))
      (node (ref "U8") (pin "5") (pinfunction "IN2_5") (pintype "input"))
    )
    (net (code "107") (name "/O17") (class "Default")
      (node (ref "IC3") (pin "2") (pinfunction "O0_2") (pintype "bidirectional"))
      (node (ref "R72") (pin "2") (pinfunction "2_2") (pintype "passive"))
      (node (ref "U9") (pin "6") (pinfunction "IN1_6") (pintype "input"))
    )
    (net (code "108") (name "/O18") (class "Default")
      (node (ref "IC3") (pin "5") (pinfunction "O1_5") (pintype "bidirectional"))
      (node (ref "R73") (pin "2") (pinfunction "2_2") (pintype "passive"))
      (node (ref "U9") (pin "5") (pinfunction "IN2_5") (pintype "input"))
    )
    (net (code "109") (name "/O19") (class "Default")
      (node (ref "IC3") (pin "6") (pinfunction "O2_6") (pintype "bidirectional"))
      (node (ref "R74") (pin "2") (pinfunction "2_2") (pintype "passive"))
      (node (ref "U10") (pin "6") (pinfunction "IN1_6") (pintype "input"))
    )
    (net (code "110") (name "/O20") (class "Default")
      (node (ref "IC3") (pin "9") (pinfunction "O3_9") (pintype "bidirectional"))
      (node (ref "R75") (pin "2") (pinfunction "2_2") (pintype "passive"))
      (node (ref "U10") (pin "5") (pinfunction "IN2_5") (pintype "input"))
    )
    (net (code "111") (name "/O21") (class "Default")
      (node (ref "IC3") (pin "12") (pinfunction "O4_12") (pintype "bidirectional"))
      (node (ref "R76") (pin "2") (pinfunction "2_2") (pintype "passive"))
      (node (ref "U11") (pin "6") (pinfunction "IN1_6") (pintype "input"))
    )
    (net (code "112") (name "/O22") (class "Default")
      (node (ref "IC3") (pin "15") (pinfunction "O5_15") (pintype "bidirectional"))
      (node (ref "R77") (pin "2") (pinfunction "2_2") (pintype "passive"))
      (node (ref "U11") (pin "5") (pinfunction "IN2_5") (pintype "input"))
    )
    (net (code "113") (name "/O23") (class "Default")
      (node (ref "IC3") (pin "16") (pinfunction "O6_16") (pintype "bidirectional"))
      (node (ref "R78") (pin "2") (pinfunction "2_2") (pintype "passive"))
      (node (ref "U12") (pin "6") (pinfunction "IN1_6") (pintype "input"))
    )
    (net (code "114") (name "/O24") (class "Default")
      (node (ref "IC3") (pin "19") (pinfunction "O7_19") (pintype "bidirectional"))
      (node (ref "R79") (pin "2") (pinfunction "2_2") (pintype "passive"))
      (node (ref "U12") (pin "5") (pinfunction "IN2_5") (pintype "input"))
    )
    (net (code "115") (name "/O25") (class "Default")
      (node (ref "IC4") (pin "2") (pinfunction "O0_2") (pintype "bidirectional"))
      (node (ref "R80") (pin "2") (pinfunction "2_2") (pintype "passive"))
      (node (ref "U13") (pin "6") (pinfunction "IN1_6") (pintype "input"))
    )
    (net (code "116") (name "/O26") (class "Default")
      (node (ref "IC4") (pin "5") (pinfunction "O1_5") (pintype "bidirectional"))
      (node (ref "R81") (pin "2") (pinfunction "2_2") (pintype "passive"))
      (node (ref "U13") (pin "5") (pinfunction "IN2_5") (pintype "input"))
    )
    (net (code "117") (name "/O27") (class "Default")
      (node (ref "IC4") (pin "6") (pinfunction "O2_6") (pintype "bidirectional"))
      (node (ref "R82") (pin "2") (pinfunction "2_2") (pintype "passive"))
      (node (ref "U14") (pin "6") (pinfunction "IN1_6") (pintype "input"))
    )
    (net (code "118") (name "/O28") (class "Default")
      (node (ref "IC4") (pin "9") (pinfunction "O3_9") (pintype "bidirectional"))
      (node (ref "R83") (pin "2") (pinfunction "2_2") (pintype "passive"))
      (node (ref "U14") (pin "5") (pinfunction "IN2_5") (pintype "input"))
    )
    (net (code "119") (name "/O29") (class "Default")
      (node (ref "IC4") (pin "12") (pinfunction "O4_12") (pintype "bidirectional"))
      (node (ref "R84") (pin "2") (pinfunction "2_2") (pintype "passive"))
      (node (ref "U15") (pin "6") (pinfunction "IN1_6") (pintype "input"))
    )
    (net (code "120") (name "/O30") (class "Default")
      (node (ref "IC4") (pin "15") (pinfunction "O5_15") (pintype "bidirectional"))
      (node (ref "R85") (pin "2") (pinfunction "2_2") (pintype "passive"))
      (node (ref "U15") (pin "5") (pinfunction "IN2_5") (pintype "input"))
    )
    (net (code "121") (name "/O31") (class "Default")
      (node (ref "IC4") (pin "16") (pinfunction "O6_16") (pintype "bidirectional"))
      (node (ref "R86") (pin "2") (pinfunction "2_2") (pintype "passive"))
      (node (ref "U16") (pin "6") (pinfunction "IN1_6") (pintype "input"))
    )
    (net (code "122") (name "/O32") (class "Default")
      (node (ref "IC4") (pin "19") (pinfunction "O7_19") (pintype "bidirectional"))
      (node (ref "R87") (pin "2") (pinfunction "2_2") (pintype "passive"))
      (node (ref "U16") (pin "5") (pinfunction "IN2_5") (pintype "input"))
    )
    (net (code "123") (name "/OE") (class "Default")
      (node (ref "IC1") (pin "1") (pinfunction "~{OE}_1") (pintype "bidirectional"))
      (node (ref "IC2") (pin "1") (pinfunction "~{OE}_1") (pintype "bidirectional"))
      (node (ref "IC3") (pin "1") (pinfunction "~{OE}_1") (pintype "bidirectional"))
      (node (ref "IC4") (pin "1") (pinfunction "~{OE}_1") (pintype "bidirectional"))
      (node (ref "J3") (pin "15") (pinfunction "GP22_15") (pintype "bidirectional"))
      (node (ref "JP4") (pin "1") (pinfunction "1_1") (pintype "passive"))
      (node (ref "OUTPUT_ENABLE") (pin "1") (pinfunction "1_1") (pintype "passive"))
    )
    (net (code "124") (name "/RXI") (class "Default")
      (node (ref "J3") (pin "10") (pinfunction "RXI_10") (pintype "input"))
      (node (ref "JP4") (pin "17") (pinfunction "17_17") (pintype "passive"))
    )
    (net (code "125") (name "/SCL") (class "Default")
      (node (ref "J3") (pin "5") (pinfunction "SCL_5") (pintype "bidirectional"))
      (node (ref "JP4") (pin "13") (pinfunction "13_13") (pintype "passive"))
    )
    (net (code "126") (name "/SCLK") (class "Default")
      (node (ref "J3") (pin "23") (pinfunction "SCLK_23") (pintype "output"))
      (node (ref "JP4") (pin "19") (pinfunction "19_19") (pintype "passive"))
    )
    (net (code "127") (name "/SDA") (class "Default")
      (node (ref "J3") (pin "3") (pinfunction "SDA_3") (pintype "bidirectional"))
      (node (ref "JP4") (pin "11") (pinfunction "11_11") (pintype "passive"))
    )
    (net (code "128") (name "/SGND") (class "Default")
      (node (ref "IC21") (pin "5") (pinfunction "LOAD_-_SWITCH_#2_1_5") (pintype "bidirectional"))
      (node (ref "IC21") (pin "8") (pinfunction "LOAD_-_SWITCH_#1_2_8") (pintype "bidirectional"))
      (node (ref "IC22") (pin "5") (pinfunction "LOAD_-_SWITCH_#2_1_5") (pintype "bidirectional"))
      (node (ref "IC22") (pin "8") (pinfunction "LOAD_-_SWITCH_#1_2_8") (pintype "bidirectional"))
      (node (ref "IC23") (pin "5") (pinfunction "LOAD_-_SWITCH_#2_1_5") (pintype "bidirectional"))
      (node (ref "IC23") (pin "8") (pinfunction "LOAD_-_SWITCH_#1_2_8") (pintype "bidirectional"))
      (node (ref "IC24") (pin "5") (pinfunction "LOAD_-_SWITCH_#2_1_5") (pintype "bidirectional"))
      (node (ref "IC24") (pin "8") (pinfunction "LOAD_-_SWITCH_#1_2_8") (pintype "bidirectional"))
      (node (ref "IC25") (pin "5") (pinfunction "LOAD_-_SWITCH_#2_1_5") (pintype "bidirectional"))
      (node (ref "IC25") (pin "8") (pinfunction "LOAD_-_SWITCH_#1_2_8") (pintype "bidirectional"))
      (node (ref "IC26") (pin "5") (pinfunction "LOAD_-_SWITCH_#2_1_5") (pintype "bidirectional"))
      (node (ref "IC26") (pin "8") (pinfunction "LOAD_-_SWITCH_#1_2_8") (pintype "bidirectional"))
      (node (ref "IC27") (pin "5") (pinfunction "LOAD_-_SWITCH_#2_1_5") (pintype "bidirectional"))
      (node (ref "IC27") (pin "8") (pinfunction "LOAD_-_SWITCH_#1_2_8") (pintype "bidirectional"))
      (node (ref "IC28") (pin "5") (pinfunction "LOAD_-_SWITCH_#2_1_5") (pintype "bidirectional"))
      (node (ref "IC28") (pin "8") (pinfunction "LOAD_-_SWITCH_#1_2_8") (pintype "bidirectional"))
      (node (ref "J2") (pin "1") (pinfunction "1_1") (pintype "passive"))
      (node (ref "JP1") (pin "1") (pinfunction "1_1") (pintype "passive"))
    )
    (net (code "129") (name "/TXO") (class "Default")
      (node (ref "J3") (pin "8") (pinfunction "TXO_8") (pintype "output"))
      (node (ref "JP4") (pin "15") (pinfunction "15_15") (pintype "passive"))
    )
    (net (code "130") (name "GND") (class "Default")
      (node (ref "C1") (pin "1") (pinfunction "1_1") (pintype "passive"))
      (node (ref "C10") (pin "1") (pinfunction "1_1") (pintype "passive"))
      (node (ref "C11") (pin "1") (pinfunction "1_1") (pintype "passive"))
      (node (ref "C12") (pin "1") (pinfunction "1_1") (pintype "passive"))
      (node (ref "C13") (pin "1") (pinfunction "1_1") (pintype "passive"))
      (node (ref "C14") (pin "1") (pinfunction "1_1") (pintype "passive"))
      (node (ref "C15") (pin "1") (pinfunction "1_1") (pintype "passive"))
      (node (ref "C16") (pin "1") (pinfunction "1_1") (pintype "passive"))
      (node (ref "C2") (pin "1") (pinfunction "1_1") (pintype "passive"))
      (node (ref "C3") (pin "1") (pinfunction "1_1") (pintype "passive"))
      (node (ref "C4") (pin "1") (pinfunction "1_1") (pintype "passive"))
      (node (ref "C5") (pin "1") (pinfunction "1_1") (pintype "passive"))
      (node (ref "C6") (pin "1") (pinfunction "1_1") (pintype "passive"))
      (node (ref "C7") (pin "1") (pinfunction "1_1") (pintype "passive"))
      (node (ref "C8") (pin "1") (pinfunction "1_1") (pintype "passive"))
      (node (ref "C9") (pin "1") (pinfunction "1_1") (pintype "passive"))
      (node (ref "IC1") (pin "10") (pinfunction "GND_10") (pintype "bidirectional"))
      (node (ref "IC10") (pin "2") (pinfunction "-_CONTROL_-_SWITCH_#1_2") (pintype "bidirectional"))
      (node (ref "IC10") (pin "4") (pinfunction "-_CONTROL_-_SWITCH_#2_4") (pintype "bidirectional"))
      (node (ref "IC11") (pin "2") (pinfunction "-_CONTROL_-_SWITCH_#1_2") (pintype "bidirectional"))
      (node (ref "IC11") (pin "4") (pinfunction "-_CONTROL_-_SWITCH_#2_4") (pintype "bidirectional"))
      (node (ref "IC12") (pin "2") (pinfunction "-_CONTROL_-_SWITCH_#1_2") (pintype "bidirectional"))
      (node (ref "IC12") (pin "4") (pinfunction "-_CONTROL_-_SWITCH_#2_4") (pintype "bidirectional"))
      (node (ref "IC13") (pin "2") (pinfunction "-_CONTROL_-_SWITCH_#1_2") (pintype "bidirectional"))
      (node (ref "IC13") (pin "4") (pinfunction "-_CONTROL_-_SWITCH_#2_4") (pintype "bidirectional"))
      (node (ref "IC14") (pin "2") (pinfunction "-_CONTROL_-_SWITCH_#1_2") (pintype "bidirectional"))
      (node (ref "IC14") (pin "4") (pinfunction "-_CONTROL_-_SWITCH_#2_4") (pintype "bidirectional"))
      (node (ref "IC15") (pin "2") (pinfunction "-_CONTROL_-_SWITCH_#1_2") (pintype "bidirectional"))
      (node (ref "IC15") (pin "4") (pinfunction "-_CONTROL_-_SWITCH_#2_4") (pintype "bidirectional"))
      (node (ref "IC16") (pin "2") (pinfunction "-_CONTROL_-_SWITCH_#1_2") (pintype "bidirectional"))
      (node (ref "IC16") (pin "4") (pinfunction "-_CONTROL_-_SWITCH_#2_4") (pintype "bidirectional"))
      (node (ref "IC17") (pin "2") (pinfunction "-_CONTROL_-_SWITCH_#1_2") (pintype "bidirectional"))
      (node (ref "IC17") (pin "4") (pinfunction "-_CONTROL_-_SWITCH_#2_4") (pintype "bidirectional"))
      (node (ref "IC18") (pin "2") (pinfunction "-_CONTROL_-_SWITCH_#1_2") (pintype "bidirectional"))
      (node (ref "IC18") (pin "4") (pinfunction "-_CONTROL_-_SWITCH_#2_4") (pintype "bidirectional"))
      (node (ref "IC19") (pin "2") (pinfunction "-_CONTROL_-_SWITCH_#1_2") (pintype "bidirectional"))
      (node (ref "IC19") (pin "4") (pinfunction "-_CONTROL_-_SWITCH_#2_4") (pintype "bidirectional"))
      (node (ref "IC2") (pin "10") (pinfunction "GND_10") (pintype "bidirectional"))
      (node (ref "IC20") (pin "2") (pinfunction "-_CONTROL_-_SWITCH_#1_2") (pintype "bidirectional"))
      (node (ref "IC20") (pin "4") (pinfunction "-_CONTROL_-_SWITCH_#2_4") (pintype "bidirectional"))
      (node (ref "IC21") (pin "2") (pinfunction "-_CONTROL_-_SWITCH_#1_2") (pintype "bidirectional"))
      (node (ref "IC21") (pin "4") (pinfunction "-_CONTROL_-_SWITCH_#2_4") (pintype "bidirectional"))
      (node (ref "IC22") (pin "2") (pinfunction "-_CONTROL_-_SWITCH_#1_2") (pintype "bidirectional"))
      (node (ref "IC22") (pin "4") (pinfunction "-_CONTROL_-_SWITCH_#2_4") (pintype "bidirectional"))
      (node (ref "IC23") (pin "2") (pinfunction "-_CONTROL_-_SWITCH_#1_2") (pintype "bidirectional"))
      (node (ref "IC23") (pin "4") (pinfunction "-_CONTROL_-_SWITCH_#2_4") (pintype "bidirectional"))
      (node (ref "IC24") (pin "2") (pinfunction "-_CONTROL_-_SWITCH_#1_2") (pintype "bidirectional"))
      (node (ref "IC24") (pin "4") (pinfunction "-_CONTROL_-_SWITCH_#2_4") (pintype "bidirectional"))
      (node (ref "IC25") (pin "2") (pinfunction "-_CONTROL_-_SWITCH_#1_2") (pintype "bidirectional"))
      (node (ref "IC25") (pin "4") (pinfunction "-_CONTROL_-_SWITCH_#2_4") (pintype "bidirectional"))
      (node (ref "IC26") (pin "2") (pinfunction "-_CONTROL_-_SWITCH_#1_2") (pintype "bidirectional"))
      (node (ref "IC26") (pin "4") (pinfunction "-_CONTROL_-_SWITCH_#2_4") (pintype "bidirectional"))
      (node (ref "IC27") (pin "2") (pinfunction "-_CONTROL_-_SWITCH_#1_2") (pintype "bidirectional"))
      (node (ref "IC27") (pin "4") (pinfunction "-_CONTROL_-_SWITCH_#2_4") (pintype "bidirectional"))
      (node (ref "IC28") (pin "2") (pinfunction "-_CONTROL_-_SWITCH_#1_2") (pintype "bidirectional"))
      (node (ref "IC28") (pin "4") (pinfunction "-_CONTROL_-_SWITCH_#2_4") (pintype "bidirectional"))
      (node (ref "IC3") (pin "10") (pinfunction "GND_10") (pintype "bidirectional"))
      (node (ref "IC4") (pin "10") (pinfunction "GND_10") (pintype "bidirectional"))
      (node (ref "IC5") (pin "2") (pinfunction "-_CONTROL_-_SWITCH_#1_2") (pintype "bidirectional"))
      (node (ref "IC5") (pin "4") (pinfunction "-_CONTROL_-_SWITCH_#2_4") (pintype "bidirectional"))
      (node (ref "IC6") (pin "2") (pinfunction "-_CONTROL_-_SWITCH_#1_2") (pintype "bidirectional"))
      (node (ref "IC6") (pin "4") (pinfunction "-_CONTROL_-_SWITCH_#2_4") (pintype "bidirectional"))
      (node (ref "IC7") (pin "2") (pinfunction "-_CONTROL_-_SWITCH_#1_2") (pintype "bidirectional"))
      (node (ref "IC7") (pin "4") (pinfunction "-_CONTROL_-_SWITCH_#2_4") (pintype "bidirectional"))
      (node (ref "IC8") (pin "2") (pinfunction "-_CONTROL_-_SWITCH_#1_2") (pintype "bidirectional"))
      (node (ref "IC8") (pin "4") (pinfunction "-_CONTROL_-_SWITCH_#2_4") (pintype "bidirectional"))
      (node (ref "IC9") (pin "2") (pinfunction "-_CONTROL_-_SWITCH_#1_2") (pintype "bidirectional"))
      (node (ref "IC9") (pin "4") (pinfunction "-_CONTROL_-_SWITCH_#2_4") (pintype "bidirectional"))
      (node (ref "J3") (pin "14") (pinfunction "GND_14") (pintype "power_in"))
      (node (ref "J3") (pin "20") (pinfunction "GND_20") (pintype "power_in"))
      (node (ref "J3") (pin "25") (pinfunction "GND_25") (pintype "power_in"))
      (node (ref "J3") (pin "30") (pinfunction "GND_30") (pintype "power_in"))
      (node (ref "J3") (pin "34") (pinfunction "GND_34") (pintype "power_in"))
      (node (ref "J3") (pin "39") (pinfunction "GND_39") (pintype "power_in"))
      (node (ref "J3") (pin "6") (pinfunction "GND_6") (pintype "power_in"))
      (node (ref "J3") (pin "9") (pinfunction "GND_9") (pintype "power_in"))
      (node (ref "J4") (pin "01") (pinfunction "01_01") (pintype "passive"))
      (node (ref "J4") (pin "03") (pinfunction "03_03") (pintype "passive"))
      (node (ref "J4") (pin "05") (pinfunction "05_05") (pintype "passive"))
      (node (ref "J4") (pin "07") (pinfunction "07_07") (pintype "passive"))
      (node (ref "J4") (pin "09") (pinfunction "09_09") (pintype "passive"))
      (node (ref "J4") (pin "11") (pinfunction "11_11") (pintype "passive"))
      (node (ref "J4") (pin "13") (pinfunction "13_13") (pintype "passive"))
      (node (ref "J4") (pin "15") (pinfunction "15_15") (pintype "passive"))
      (node (ref "J7") (pin "01") (pinfunction "01_01") (pintype "passive"))
      (node (ref "J7") (pin "03") (pinfunction "03_03") (pintype "passive"))
      (node (ref "J7") (pin "05") (pinfunction "05_05") (pintype "passive"))
      (node (ref "J7") (pin "07") (pinfunction "07_07") (pintype "passive"))
      (node (ref "J7") (pin "09") (pinfunction "09_09") (pintype "passive"))
      (node (ref "J7") (pin "11") (pinfunction "11_11") (pintype "passive"))
      (node (ref "J7") (pin "13") (pinfunction "13_13") (pintype "passive"))
      (node (ref "J7") (pin "15") (pinfunction "15_15") (pintype "passive"))
      (node (ref "JP4") (pin "10") (pinfunction "10_10") (pintype "passive"))
      (node (ref "JP4") (pin "12") (pinfunction "12_12") (pintype "passive"))
      (node (ref "JP4") (pin "14") (pinfunction "14_14") (pintype "passive"))
      (node (ref "JP4") (pin "16") (pinfunction "16_16") (pintype "passive"))
      (node (ref "JP4") (pin "18") (pinfunction "18_18") (pintype "passive"))
      (node (ref "JP4") (pin "2") (pinfunction "2_2") (pintype "passive"))
      (node (ref "JP4") (pin "20") (pinfunction "20_20") (pintype "passive"))
      (node (ref "JP4") (pin "22") (pinfunction "22_22") (pintype "passive"))
      (node (ref "JP4") (pin "24") (pinfunction "24_24") (pintype "passive"))
      (node (ref "JP4") (pin "26") (pinfunction "26_26") (pintype "passive"))
      (node (ref "JP4") (pin "28") (pinfunction "28_28") (pintype "passive"))
      (node (ref "JP4") (pin "30") (pinfunction "30_30") (pintype "passive"))
      (node (ref "JP4") (pin "32") (pinfunction "32_32") (pintype "passive"))
      (node (ref "JP4") (pin "34") (pinfunction "34_34") (pintype "passive"))
      (node (ref "JP4") (pin "36") (pinfunction "36_36") (pintype "passive"))
      (node (ref "JP4") (pin "38") (pinfunction "38_38") (pintype "passive"))
      (node (ref "JP4") (pin "4") (pinfunction "4_4") (pintype "passive"))
      (node (ref "JP4") (pin "40") (pinfunction "40_40") (pintype "passive"))
      (node (ref "JP4") (pin "6") (pinfunction "6_6") (pintype "passive"))
      (node (ref "JP4") (pin "8") (pinfunction "8_8") (pintype "passive"))
      (node (ref "POWER") (pin "1") (pinfunction "1_1") (pintype "passive"))
      (node (ref "R1") (pin "1") (pinfunction "1_1") (pintype "passive"))
      (node (ref "R2") (pin "1") (pinfunction "1_1") (pintype "passive"))
      (node (ref "R3") (pin "1") (pinfunction "1_1") (pintype "passive"))
      (node (ref "R4") (pin "1") (pinfunction "1_1") (pintype "passive"))
      (node (ref "R55") (pin "1") (pinfunction "1_1") (pintype "passive"))
      (node (ref "R56") (pin "1") (pinfunction "1_1") (pintype "passive"))
      (node (ref "R57") (pin "1") (pinfunction "1_1") (pintype "passive"))
      (node (ref "R58") (pin "1") (pinfunction "1_1") (pintype "passive"))
      (node (ref "R60") (pin "1") (pinfunction "1_1") (pintype "passive"))
      (node (ref "R61") (pin "1") (pinfunction "1_1") (pintype "passive"))
      (node (ref "R62") (pin "1") (pinfunction "1_1") (pintype "passive"))
      (node (ref "R63") (pin "1") (pinfunction "1_1") (pintype "passive"))
      (node (ref "R64") (pin "1") (pinfunction "1_1") (pintype "passive"))
      (node (ref "R65") (pin "1") (pinfunction "1_1") (pintype "passive"))
      (node (ref "R66") (pin "1") (pinfunction "1_1") (pintype "passive"))
      (node (ref "R67") (pin "1") (pinfunction "1_1") (pintype "passive"))
      (node (ref "R68") (pin "1") (pinfunction "1_1") (pintype "passive"))
      (node (ref "R69") (pin "1") (pinfunction "1_1") (pintype "passive"))
      (node (ref "R70") (pin "1") (pinfunction "1_1") (pintype "passive"))
      (node (ref "R71") (pin "1") (pinfunction "1_1") (pintype "passive"))
      (node (ref "R72") (pin "1") (pinfunction "1_1") (pintype "passive"))
      (node (ref "R73") (pin "1") (pinfunction "1_1") (pintype "passive"))
      (node (ref "R74") (pin "1") (pinfunction "1_1") (pintype "passive"))
      (node (ref "R75") (pin "1") (pinfunction "1_1") (pintype "passive"))
      (node (ref "R76") (pin "1") (pinfunction "1_1") (pintype "passive"))
      (node (ref "R77") (pin "1") (pinfunction "1_1") (pintype "passive"))
      (node (ref "R78") (pin "1") (pinfunction "1_1") (pintype "passive"))
      (node (ref "R79") (pin "1") (pinfunction "1_1") (pintype "passive"))
      (node (ref "R80") (pin "1") (pinfunction "1_1") (pintype "passive"))
      (node (ref "R81") (pin "1") (pinfunction "1_1") (pintype "passive"))
      (node (ref "R82") (pin "1") (pinfunction "1_1") (pintype "passive"))
      (node (ref "R83") (pin "1") (pinfunction "1_1") (pintype "passive"))
      (node (ref "R84") (pin "1") (pinfunction "1_1") (pintype "passive"))
      (node (ref "R85") (pin "1") (pinfunction "1_1") (pintype "passive"))
      (node (ref "R86") (pin "1") (pinfunction "1_1") (pintype "passive"))
      (node (ref "R87") (pin "1") (pinfunction "1_1") (pintype "passive"))
      (node (ref "U1") (pin "4") (pinfunction "GND_4") (pintype "power_in"))
      (node (ref "U10") (pin "4") (pinfunction "GND_4") (pintype "power_in"))
      (node (ref "U11") (pin "4") (pinfunction "GND_4") (pintype "power_in"))
      (node (ref "U12") (pin "4") (pinfunction "GND_4") (pintype "power_in"))
      (node (ref "U13") (pin "4") (pinfunction "GND_4") (pintype "power_in"))
      (node (ref "U14") (pin "4") (pinfunction "GND_4") (pintype "power_in"))
      (node (ref "U15") (pin "4") (pinfunction "GND_4") (pintype "power_in"))
      (node (ref "U16") (pin "4") (pinfunction "GND_4") (pintype "power_in"))
      (node (ref "U2") (pin "4") (pinfunction "GND_4") (pintype "power_in"))
      (node (ref "U3") (pin "4") (pinfunction "GND_4") (pintype "power_in"))
      (node (ref "U4") (pin "4") (pinfunction "GND_4") (pintype "power_in"))
      (node (ref "U5") (pin "4") (pinfunction "GND_4") (pintype "power_in"))
      (node (ref "U6") (pin "4") (pinfunction "GND_4") (pintype "power_in"))
      (node (ref "U7") (pin "4") (pinfunction "GND_4") (pintype "power_in"))
      (node (ref "U8") (pin "4") (pinfunction "GND_4") (pintype "power_in"))
      (node (ref "U9") (pin "4") (pinfunction "GND_4") (pintype "power_in"))
    )
    (net (code "131") (name "Net-(IC5-+_CONTROL_-_SWITCH_#1)") (class "Default")
      (node (ref "IC5") (pin "1") (pinfunction "+_CONTROL_-_SWITCH_#1_1") (pintype "bidirectional"))
      (node (ref "R6") (pin "1") (pinfunction "1_1") (pintype "passive"))
    )
    (net (code "132") (name "Net-(IC5-+_CONTROL_-_SWITCH_#2)") (class "Default")
      (node (ref "IC5") (pin "3") (pinfunction "+_CONTROL_-_SWITCH_#2_3") (pintype "bidirectional"))
      (node (ref "R7") (pin "1") (pinfunction "1_1") (pintype "passive"))
    )
    (net (code "133") (name "Net-(IC6-+_CONTROL_-_SWITCH_#1)") (class "Default")
      (node (ref "IC6") (pin "1") (pinfunction "+_CONTROL_-_SWITCH_#1_1") (pintype "bidirectional"))
      (node (ref "R8") (pin "1") (pinfunction "1_1") (pintype "passive"))
    )
    (net (code "134") (name "Net-(IC6-+_CONTROL_-_SWITCH_#2)") (class "Default")
      (node (ref "IC6") (pin "3") (pinfunction "+_CONTROL_-_SWITCH_#2_3") (pintype "bidirectional"))
      (node (ref "R9") (pin "1") (pinfunction "1_1") (pintype "passive"))
    )
    (net (code "135") (name "Net-(IC7-+_CONTROL_-_SWITCH_#1)") (class "Default")
      (node (ref "IC7") (pin "1") (pinfunction "+_CONTROL_-_SWITCH_#1_1") (pintype "bidirectional"))
      (node (ref "R10") (pin "1") (pinfunction "1_1") (pintype "passive"))
    )
    (net (code "136") (name "Net-(IC7-+_CONTROL_-_SWITCH_#2)") (class "Default")
      (node (ref "IC7") (pin "3") (pinfunction "+_CONTROL_-_SWITCH_#2_3") (pintype "bidirectional"))
      (node (ref "R11") (pin "1") (pinfunction "1_1") (pintype "passive"))
    )
    (net (code "137") (name "Net-(IC8-+_CONTROL_-_SWITCH_#1)") (class "Default")
      (node (ref "IC8") (pin "1") (pinfunction "+_CONTROL_-_SWITCH_#1_1") (pintype "bidirectional"))
      (node (ref "R12") (pin "1") (pinfunction "1_1") (pintype "passive"))
    )
    (net (code "138") (name "Net-(IC8-+_CONTROL_-_SWITCH_#2)") (class "Default")
      (node (ref "IC8") (pin "3") (pinfunction "+_CONTROL_-_SWITCH_#2_3") (pintype "bidirectional"))
      (node (ref "R13") (pin "1") (pinfunction "1_1") (pintype "passive"))
    )
    (net (code "139") (name "Net-(IC9-+_CONTROL_-_SWITCH_#1)") (class "Default")
      (node (ref "IC9") (pin "1") (pinfunction "+_CONTROL_-_SWITCH_#1_1") (pintype "bidirectional"))
      (node (ref "R14") (pin "1") (pinfunction "1_1") (pintype "passive"))
    )
    (net (code "140") (name "Net-(IC9-+_CONTROL_-_SWITCH_#2)") (class "Default")
      (node (ref "IC9") (pin "3") (pinfunction "+_CONTROL_-_SWITCH_#2_3") (pintype "bidirectional"))
      (node (ref "R15") (pin "1") (pinfunction "1_1") (pintype "passive"))
    )
    (net (code "141") (name "Net-(IC10-+_CONTROL_-_SWITCH_#1)") (class "Default")
      (node (ref "IC10") (pin "1") (pinfunction "+_CONTROL_-_SWITCH_#1_1") (pintype "bidirectional"))
      (node (ref "R16") (pin "1") (pinfunction "1_1") (pintype "passive"))
    )
    (net (code "142") (name "Net-(IC10-+_CONTROL_-_SWITCH_#2)") (class "Default")
      (node (ref "IC10") (pin "3") (pinfunction "+_CONTROL_-_SWITCH_#2_3") (pintype "bidirectional"))
      (node (ref "R17") (pin "1") (pinfunction "1_1") (pintype "passive"))
    )
    (net (code "143") (name "Net-(IC11-+_CONTROL_-_SWITCH_#1)") (class "Default")
      (node (ref "IC11") (pin "1") (pinfunction "+_CONTROL_-_SWITCH_#1_1") (pintype "bidirectional"))
      (node (ref "R18") (pin "1") (pinfunction "1_1") (pintype "passive"))
    )
    (net (code "144") (name "Net-(IC11-+_CONTROL_-_SWITCH_#2)") (class "Default")
      (node (ref "IC11") (pin "3") (pinfunction "+_CONTROL_-_SWITCH_#2_3") (pintype "bidirectional"))
      (node (ref "R19") (pin "1") (pinfunction "1_1") (pintype "passive"))
    )
    (net (code "145") (name "Net-(IC12-+_CONTROL_-_SWITCH_#1)") (class "Default")
      (node (ref "IC12") (pin "1") (pinfunction "+_CONTROL_-_SWITCH_#1_1") (pintype "bidirectional"))
      (node (ref "R20") (pin "1") (pinfunction "1_1") (pintype "passive"))
    )
    (net (code "146") (name "Net-(IC12-+_CONTROL_-_SWITCH_#2)") (class "Default")
      (node (ref "IC12") (pin "3") (pinfunction "+_CONTROL_-_SWITCH_#2_3") (pintype "bidirectional"))
      (node (ref "R21") (pin "1") (pinfunction "1_1") (pintype "passive"))
    )
    (net (code "147") (name "Net-(IC13-+_CONTROL_-_SWITCH_#1)") (class "Default")
      (node (ref "IC13") (pin "1") (pinfunction "+_CONTROL_-_SWITCH_#1_1") (pintype "bidirectional"))
      (node (ref "R38") (pin "1") (pinfunction "1_1") (pintype "passive"))
    )
    (net (code "148") (name "Net-(IC13-+_CONTROL_-_SWITCH_#2)") (class "Default")
      (node (ref "IC13") (pin "3") (pinfunction "+_CONTROL_-_SWITCH_#2_3") (pintype "bidirectional"))
      (node (ref "R39") (pin "1") (pinfunction "1_1") (pintype "passive"))
    )
    (net (code "149") (name "Net-(IC14-+_CONTROL_-_SWITCH_#1)") (class "Default")
      (node (ref "IC14") (pin "1") (pinfunction "+_CONTROL_-_SWITCH_#1_1") (pintype "bidirectional"))
      (node (ref "R40") (pin "1") (pinfunction "1_1") (pintype "passive"))
    )
    (net (code "150") (name "Net-(IC14-+_CONTROL_-_SWITCH_#2)") (class "Default")
      (node (ref "IC14") (pin "3") (pinfunction "+_CONTROL_-_SWITCH_#2_3") (pintype "bidirectional"))
      (node (ref "R41") (pin "1") (pinfunction "1_1") (pintype "passive"))
    )
    (net (code "151") (name "Net-(IC15-+_CONTROL_-_SWITCH_#1)") (class "Default")
      (node (ref "IC15") (pin "1") (pinfunction "+_CONTROL_-_SWITCH_#1_1") (pintype "bidirectional"))
      (node (ref "R42") (pin "1") (pinfunction "1_1") (pintype "passive"))
    )
    (net (code "152") (name "Net-(IC15-+_CONTROL_-_SWITCH_#2)") (class "Default")
      (node (ref "IC15") (pin "3") (pinfunction "+_CONTROL_-_SWITCH_#2_3") (pintype "bidirectional"))
      (node (ref "R43") (pin "1") (pinfunction "1_1") (pintype "passive"))
    )
    (net (code "153") (name "Net-(IC16-+_CONTROL_-_SWITCH_#1)") (class "Default")
      (node (ref "IC16") (pin "1") (pinfunction "+_CONTROL_-_SWITCH_#1_1") (pintype "bidirectional"))
      (node (ref "R44") (pin "1") (pinfunction "1_1") (pintype "passive"))
    )
    (net (code "154") (name "Net-(IC16-+_CONTROL_-_SWITCH_#2)") (class "Default")
      (node (ref "IC16") (pin "3") (pinfunction "+_CONTROL_-_SWITCH_#2_3") (pintype "bidirectional"))
      (node (ref "R45") (pin "1") (pinfunction "1_1") (pintype "passive"))
    )
    (net (code "155") (name "Net-(IC17-+_CONTROL_-_SWITCH_#1)") (class "Default")
      (node (ref "IC17") (pin "1") (pinfunction "+_CONTROL_-_SWITCH_#1_1") (pintype "bidirectional"))
      (node (ref "R46") (pin "1") (pinfunction "1_1") (pintype "passive"))
    )
    (net (code "156") (name "Net-(IC17-+_CONTROL_-_SWITCH_#2)") (class "Default")
      (node (ref "IC17") (pin "3") (pinfunction "+_CONTROL_-_SWITCH_#2_3") (pintype "bidirectional"))
      (node (ref "R47") (pin "1") (pinfunction "1_1") (pintype "passive"))
    )
    (net (code "157") (name "Net-(IC18-+_CONTROL_-_SWITCH_#1)") (class "Default")
      (node (ref "IC18") (pin "1") (pinfunction "+_CONTROL_-_SWITCH_#1_1") (pintype "bidirectional"))
      (node (ref "R48") (pin "1") (pinfunction "1_1") (pintype "passive"))
    )
    (net (code "158") (name "Net-(IC18-+_CONTROL_-_SWITCH_#2)") (class "Default")
      (node (ref "IC18") (pin "3") (pinfunction "+_CONTROL_-_SWITCH_#2_3") (pintype "bidirectional"))
      (node (ref "R49") (pin "1") (pinfunction "1_1") (pintype "passive"))
    )
    (net (code "159") (name "Net-(IC19-+_CONTROL_-_SWITCH_#1)") (class "Default")
      (node (ref "IC19") (pin "1") (pinfunction "+_CONTROL_-_SWITCH_#1_1") (pintype "bidirectional"))
      (node (ref "R50") (pin "1") (pinfunction "1_1") (pintype "passive"))
    )
    (net (code "160") (name "Net-(IC19-+_CONTROL_-_SWITCH_#2)") (class "Default")
      (node (ref "IC19") (pin "3") (pinfunction "+_CONTROL_-_SWITCH_#2_3") (pintype "bidirectional"))
      (node (ref "R51") (pin "1") (pinfunction "1_1") (pintype "passive"))
    )
    (net (code "161") (name "Net-(IC20-+_CONTROL_-_SWITCH_#1)") (class "Default")
      (node (ref "IC20") (pin "1") (pinfunction "+_CONTROL_-_SWITCH_#1_1") (pintype "bidirectional"))
      (node (ref "R52") (pin "1") (pinfunction "1_1") (pintype "passive"))
    )
    (net (code "162") (name "Net-(IC20-+_CONTROL_-_SWITCH_#2)") (class "Default")
      (node (ref "IC20") (pin "3") (pinfunction "+_CONTROL_-_SWITCH_#2_3") (pintype "bidirectional"))
      (node (ref "R53") (pin "1") (pinfunction "1_1") (pintype "passive"))
    )
    (net (code "163") (name "Net-(IC21-+_CONTROL_-_SWITCH_#1)") (class "Default")
      (node (ref "IC21") (pin "1") (pinfunction "+_CONTROL_-_SWITCH_#1_1") (pintype "bidirectional"))
      (node (ref "R22") (pin "1") (pinfunction "1_1") (pintype "passive"))
    )
    (net (code "164") (name "Net-(IC21-+_CONTROL_-_SWITCH_#2)") (class "Default")
      (node (ref "IC21") (pin "3") (pinfunction "+_CONTROL_-_SWITCH_#2_3") (pintype "bidirectional"))
      (node (ref "R23") (pin "1") (pinfunction "1_1") (pintype "passive"))
    )
    (net (code "165") (name "Net-(IC22-+_CONTROL_-_SWITCH_#1)") (class "Default")
      (node (ref "IC22") (pin "1") (pinfunction "+_CONTROL_-_SWITCH_#1_1") (pintype "bidirectional"))
      (node (ref "R24") (pin "1") (pinfunction "1_1") (pintype "passive"))
    )
    (net (code "166") (name "Net-(IC22-+_CONTROL_-_SWITCH_#2)") (class "Default")
      (node (ref "IC22") (pin "3") (pinfunction "+_CONTROL_-_SWITCH_#2_3") (pintype "bidirectional"))
      (node (ref "R25") (pin "1") (pinfunction "1_1") (pintype "passive"))
    )
    (net (code "167") (name "Net-(IC23-+_CONTROL_-_SWITCH_#1)") (class "Default")
      (node (ref "IC23") (pin "1") (pinfunction "+_CONTROL_-_SWITCH_#1_1") (pintype "bidirectional"))
      (node (ref "R26") (pin "1") (pinfunction "1_1") (pintype "passive"))
    )
    (net (code "168") (name "Net-(IC23-+_CONTROL_-_SWITCH_#2)") (class "Default")
      (node (ref "IC23") (pin "3") (pinfunction "+_CONTROL_-_SWITCH_#2_3") (pintype "bidirectional"))
      (node (ref "R27") (pin "1") (pinfunction "1_1") (pintype "passive"))
    )
    (net (code "169") (name "Net-(IC24-+_CONTROL_-_SWITCH_#1)") (class "Default")
      (node (ref "IC24") (pin "1") (pinfunction "+_CONTROL_-_SWITCH_#1_1") (pintype "bidirectional"))
      (node (ref "R28") (pin "1") (pinfunction "1_1") (pintype "passive"))
    )
    (net (code "170") (name "Net-(IC24-+_CONTROL_-_SWITCH_#2)") (class "Default")
      (node (ref "IC24") (pin "3") (pinfunction "+_CONTROL_-_SWITCH_#2_3") (pintype "bidirectional"))
      (node (ref "R29") (pin "1") (pinfunction "1_1") (pintype "passive"))
    )
    (net (code "171") (name "Net-(IC25-+_CONTROL_-_SWITCH_#1)") (class "Default")
      (node (ref "IC25") (pin "1") (pinfunction "+_CONTROL_-_SWITCH_#1_1") (pintype "bidirectional"))
      (node (ref "R30") (pin "1") (pinfunction "1_1") (pintype "passive"))
    )
    (net (code "172") (name "Net-(IC25-+_CONTROL_-_SWITCH_#2)") (class "Default")
      (node (ref "IC25") (pin "3") (pinfunction "+_CONTROL_-_SWITCH_#2_3") (pintype "bidirectional"))
      (node (ref "R31") (pin "1") (pinfunction "1_1") (pintype "passive"))
    )
    (net (code "173") (name "Net-(IC26-+_CONTROL_-_SWITCH_#1)") (class "Default")
      (node (ref "IC26") (pin "1") (pinfunction "+_CONTROL_-_SWITCH_#1_1") (pintype "bidirectional"))
      (node (ref "R32") (pin "1") (pinfunction "1_1") (pintype "passive"))
    )
    (net (code "174") (name "Net-(IC26-+_CONTROL_-_SWITCH_#2)") (class "Default")
      (node (ref "IC26") (pin "3") (pinfunction "+_CONTROL_-_SWITCH_#2_3") (pintype "bidirectional"))
      (node (ref "R33") (pin "1") (pinfunction "1_1") (pintype "passive"))
    )
    (net (code "175") (name "Net-(IC27-+_CONTROL_-_SWITCH_#1)") (class "Default")
      (node (ref "IC27") (pin "1") (pinfunction "+_CONTROL_-_SWITCH_#1_1") (pintype "bidirectional"))
      (node (ref "R34") (pin "1") (pinfunction "1_1") (pintype "passive"))
    )
    (net (code "176") (name "Net-(IC27-+_CONTROL_-_SWITCH_#2)") (class "Default")
      (node (ref "IC27") (pin "3") (pinfunction "+_CONTROL_-_SWITCH_#2_3") (pintype "bidirectional"))
      (node (ref "R35") (pin "1") (pinfunction "1_1") (pintype "passive"))
    )
    (net (code "177") (name "Net-(IC28-+_CONTROL_-_SWITCH_#1)") (class "Default")
      (node (ref "IC28") (pin "1") (pinfunction "+_CONTROL_-_SWITCH_#1_1") (pintype "bidirectional"))
      (node (ref "R36") (pin "1") (pinfunction "1_1") (pintype "passive"))
    )
    (net (code "178") (name "Net-(IC28-+_CONTROL_-_SWITCH_#2)") (class "Default")
      (node (ref "IC28") (pin "3") (pinfunction "+_CONTROL_-_SWITCH_#2_3") (pintype "bidirectional"))
      (node (ref "R37") (pin "1") (pinfunction "1_1") (pintype "passive"))
    )
    (net (code "179") (name "Net-(POWER-Pad2)") (class "Default")
      (node (ref "POWER") (pin "2") (pinfunction "2_2") (pintype "passive"))
      (node (ref "R54") (pin "2") (pinfunction "2_2") (pintype "passive"))
    )
    (net (code "180") (name "VDD") (class "Default")
      (node (ref "C1") (pin "2") (pinfunction "2_2") (pintype "passive"))
      (node (ref "C10") (pin "2") (pinfunction "2_2") (pintype "passive"))
      (node (ref "C11") (pin "2") (pinfunction "2_2") (pintype "passive"))
      (node (ref "C12") (pin "2") (pinfunction "2_2") (pintype "passive"))
      (node (ref "C13") (pin "2") (pinfunction "2_2") (pintype "passive"))
      (node (ref "C14") (pin "2") (pinfunction "2_2") (pintype "passive"))
      (node (ref "C15") (pin "2") (pinfunction "2_2") (pintype "passive"))
      (node (ref "C16") (pin "2") (pinfunction "2_2") (pintype "passive"))
      (node (ref "C2") (pin "2") (pinfunction "2_2") (pintype "passive"))
      (node (ref "C3") (pin "2") (pinfunction "2_2") (pintype "passive"))
      (node (ref "C4") (pin "2") (pinfunction "2_2") (pintype "passive"))
      (node (ref "C5") (pin "2") (pinfunction "2_2") (pintype "passive"))
      (node (ref "C6") (pin "2") (pinfunction "2_2") (pintype "passive"))
      (node (ref "C7") (pin "2") (pinfunction "2_2") (pintype "passive"))
      (node (ref "C8") (pin "2") (pinfunction "2_2") (pintype "passive"))
      (node (ref "C9") (pin "2") (pinfunction "2_2") (pintype "passive"))
      (node (ref "IC1") (pin "20") (pinfunction "VCC_20") (pintype "bidirectional"))
      (node (ref "IC2") (pin "20") (pinfunction "VCC_20") (pintype "bidirectional"))
      (node (ref "IC3") (pin "20") (pinfunction "VCC_20") (pintype "bidirectional"))
      (node (ref "IC4") (pin "20") (pinfunction "VCC_20") (pintype "bidirectional"))
      (node (ref "J3") (pin "2") (pinfunction "5V_2") (pintype "power_in"))
      (node (ref "J3") (pin "4") (pinfunction "5V_4") (pintype "power_in"))
      (node (ref "JP4") (pin "37") (pinfunction "37_37") (pintype "passive"))
      (node (ref "JP4") (pin "39") (pinfunction "39_39") (pintype "passive"))
      (node (ref "R54") (pin "1") (pinfunction "1_1") (pintype "passive"))
      (node (ref "R59") (pin "2") (pinfunction "2_2") (pintype "passive"))
      (node (ref "U1") (pin "7") (pinfunction "COM_7") (pintype "bidirectional"))
      (node (ref "U1") (pin "8") (pinfunction "VCC_8") (pintype "power_in"))
      (node (ref "U10") (pin "7") (pinfunction "COM_7") (pintype "bidirectional"))
      (node (ref "U10") (pin "8") (pinfunction "VCC_8") (pintype "power_in"))
      (node (ref "U11") (pin "7") (pinfunction "COM_7") (pintype "bidirectional"))
      (node (ref "U11") (pin "8") (pinfunction "VCC_8") (pintype "power_in"))
      (node (ref "U12") (pin "7") (pinfunction "COM_7") (pintype "bidirectional"))
      (node (ref "U12") (pin "8") (pinfunction "VCC_8") (pintype "power_in"))
      (node (ref "U13") (pin "7") (pinfunction "COM_7") (pintype "bidirectional"))
      (node (ref "U13") (pin "8") (pinfunction "VCC_8") (pintype "power_in"))
      (node (ref "U14") (pin "7") (pinfunction "COM_7") (pintype "bidirectional"))
      (node (ref "U14") (pin "8") (pinfunction "VCC_8") (pintype "power_in"))
      (node (ref "U15") (pin "7") (pinfunction "COM_7") (pintype "bidirectional"))
      (node (ref "U15") (pin "8") (pinfunction "VCC_8") (pintype "power_in"))
      (node (ref "U16") (pin "7") (pinfunction "COM_7") (pintype "bidirectional"))
      (node (ref "U16") (pin "8") (pinfunction "VCC_8") (pintype "power_in"))
      (node (ref "U2") (pin "7") (pinfunction "COM_7") (pintype "bidirectional"))
      (node (ref "U2") (pin "8") (pinfunction "VCC_8") (pintype "power_in"))
      (node (ref "U3") (pin "7") (pinfunction "COM_7") (pintype "bidirectional"))
      (node (ref "U3") (pin "8") (pinfunction "VCC_8") (pintype "power_in"))
      (node (ref "U4") (pin "7") (pinfunction "COM_7") (pintype "bidirectional"))
      (node (ref "U4") (pin "8") (pinfunction "VCC_8") (pintype "power_in"))
      (node (ref "U5") (pin "7") (pinfunction "COM_7") (pintype "bidirectional"))
      (node (ref "U5") (pin "8") (pinfunction "VCC_8") (pintype "power_in"))
      (node (ref "U6") (pin "7") (pinfunction "COM_7") (pintype "bidirectional"))
      (node (ref "U6") (pin "8") (pinfunction "VCC_8") (pintype "power_in"))
      (node (ref "U7") (pin "7") (pinfunction "COM_7") (pintype "bidirectional"))
      (node (ref "U7") (pin "8") (pinfunction "VCC_8") (pintype "power_in"))
      (node (ref "U8") (pin "7") (pinfunction "COM_7") (pintype "bidirectional"))
      (node (ref "U8") (pin "8") (pinfunction "VCC_8") (pintype "power_in"))
      (node (ref "U9") (pin "7") (pinfunction "COM_7") (pintype "bidirectional"))
      (node (ref "U9") (pin "8") (pinfunction "VCC_8") (pintype "power_in"))
    )
    (net (code "181") (name "unconnected-(J5-Pad1)") (class "Default")
      (node (ref "J5") (pin "1") (pinfunction "1_1") (pintype "bidirectional"))
    )
    (net (code "182") (name "unconnected-(J5-Pad2)") (class "Default")
      (node (ref "J5") (pin "2") (pinfunction "2_2") (pintype "bidirectional"))
    )
    (net (code "183") (name "unconnected-(J5-Pad3)") (class "Default")
      (node (ref "J5") (pin "3") (pinfunction "3_3") (pintype "bidirectional"))
    )
    (net (code "184") (name "unconnected-(J5-Pad4)") (class "Default")
      (node (ref "J5") (pin "4") (pinfunction "4_4") (pintype "bidirectional"))
    )
    (net (code "185") (name "unconnected-(J6-Pad1)") (class "Default")
      (node (ref "J6") (pin "1") (pinfunction "1_1") (pintype "bidirectional"))
    )
    (net (code "186") (name "unconnected-(J6-Pad2)") (class "Default")
      (node (ref "J6") (pin "2") (pinfunction "2_2") (pintype "bidirectional"))
    )
    (net (code "187") (name "unconnected-(J6-Pad3)") (class "Default")
      (node (ref "J6") (pin "3") (pinfunction "3_3") (pintype "bidirectional"))
    )
    (net (code "188") (name "unconnected-(J6-Pad4)") (class "Default")
      (node (ref "J6") (pin "4") (pinfunction "4_4") (pintype "bidirectional"))
    )
  )
)
